# LM_180622.net
KiCad netlist of a schematic drawn in EAGLE
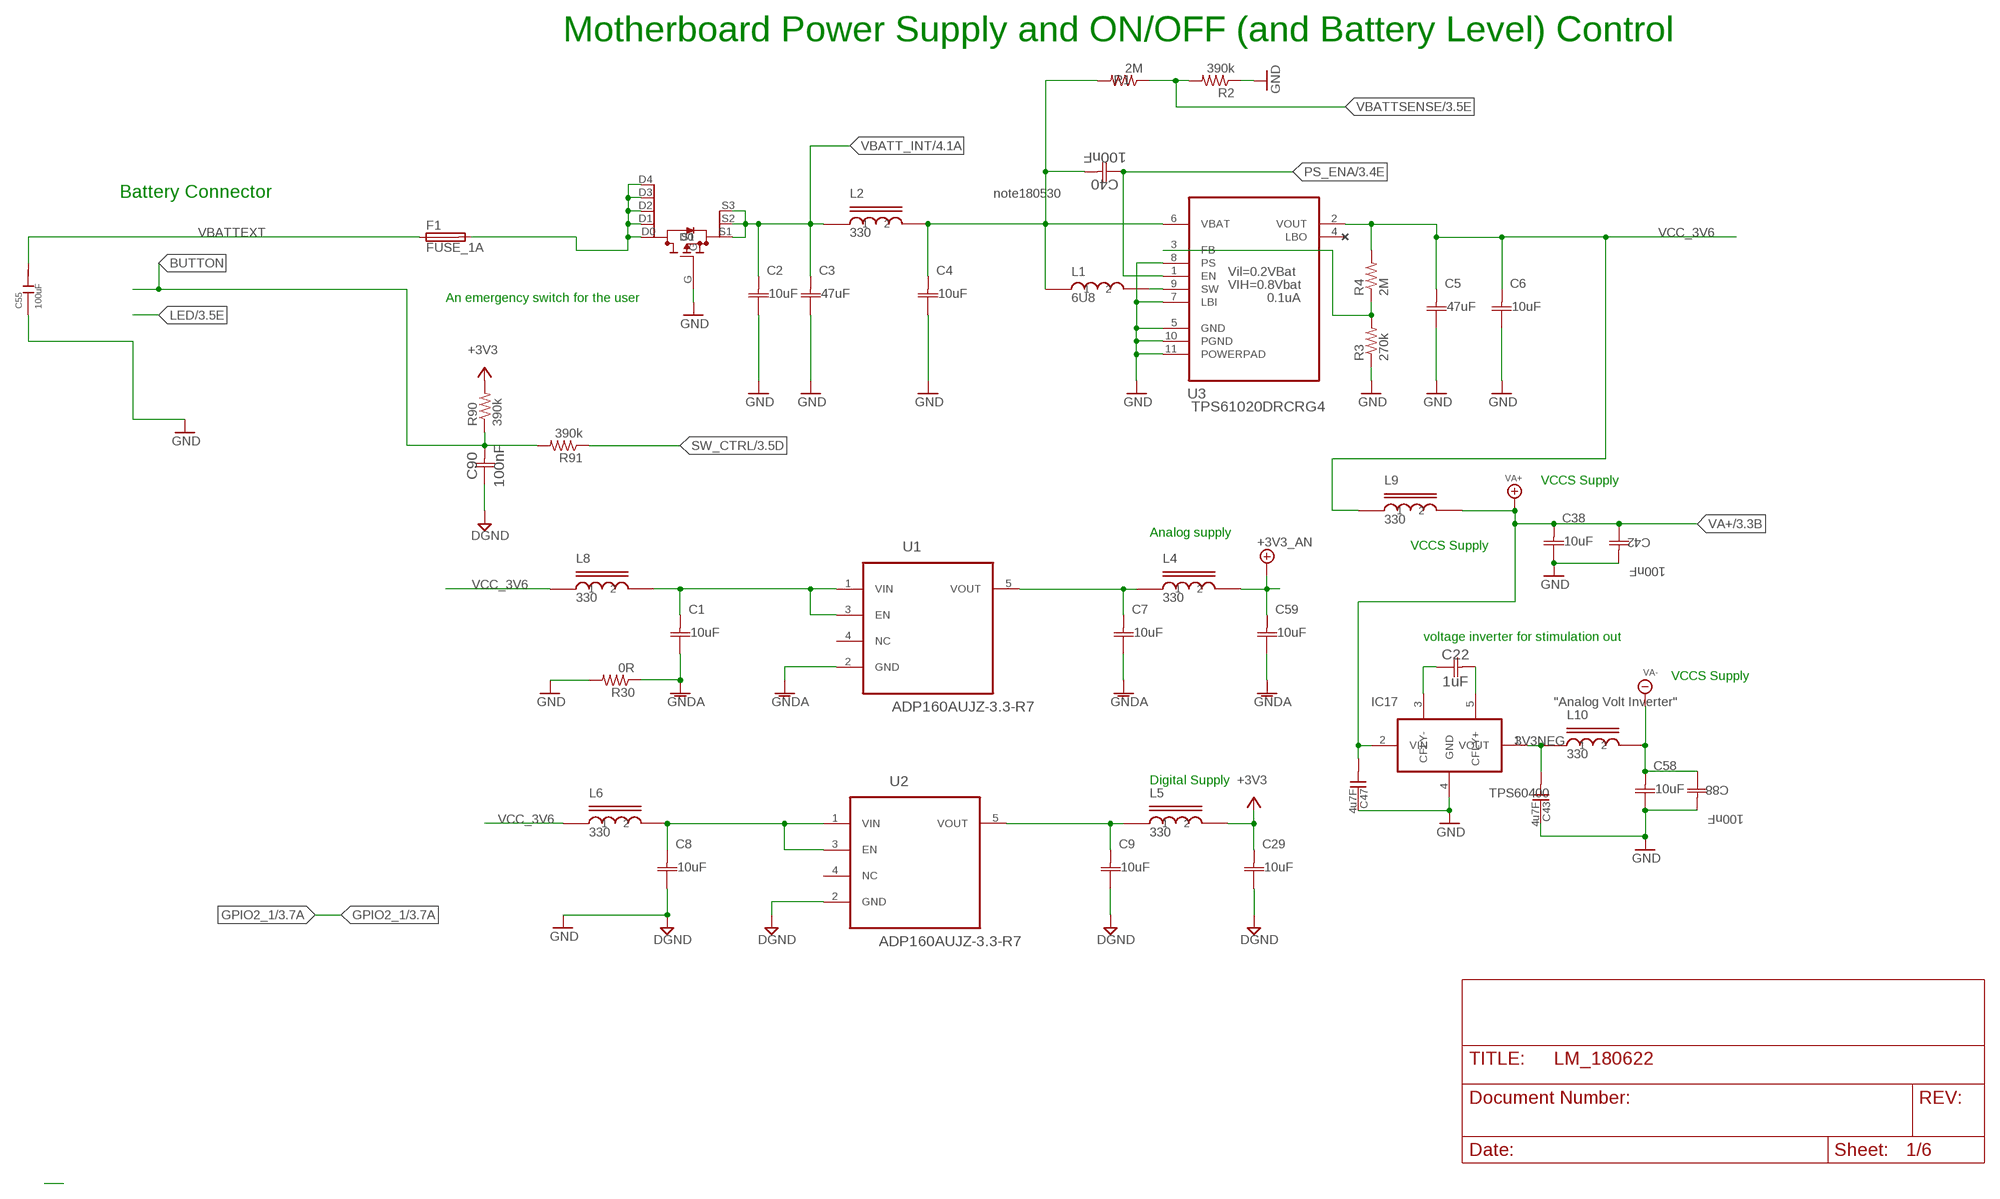
[diagram p0: schematic, sheet 1]
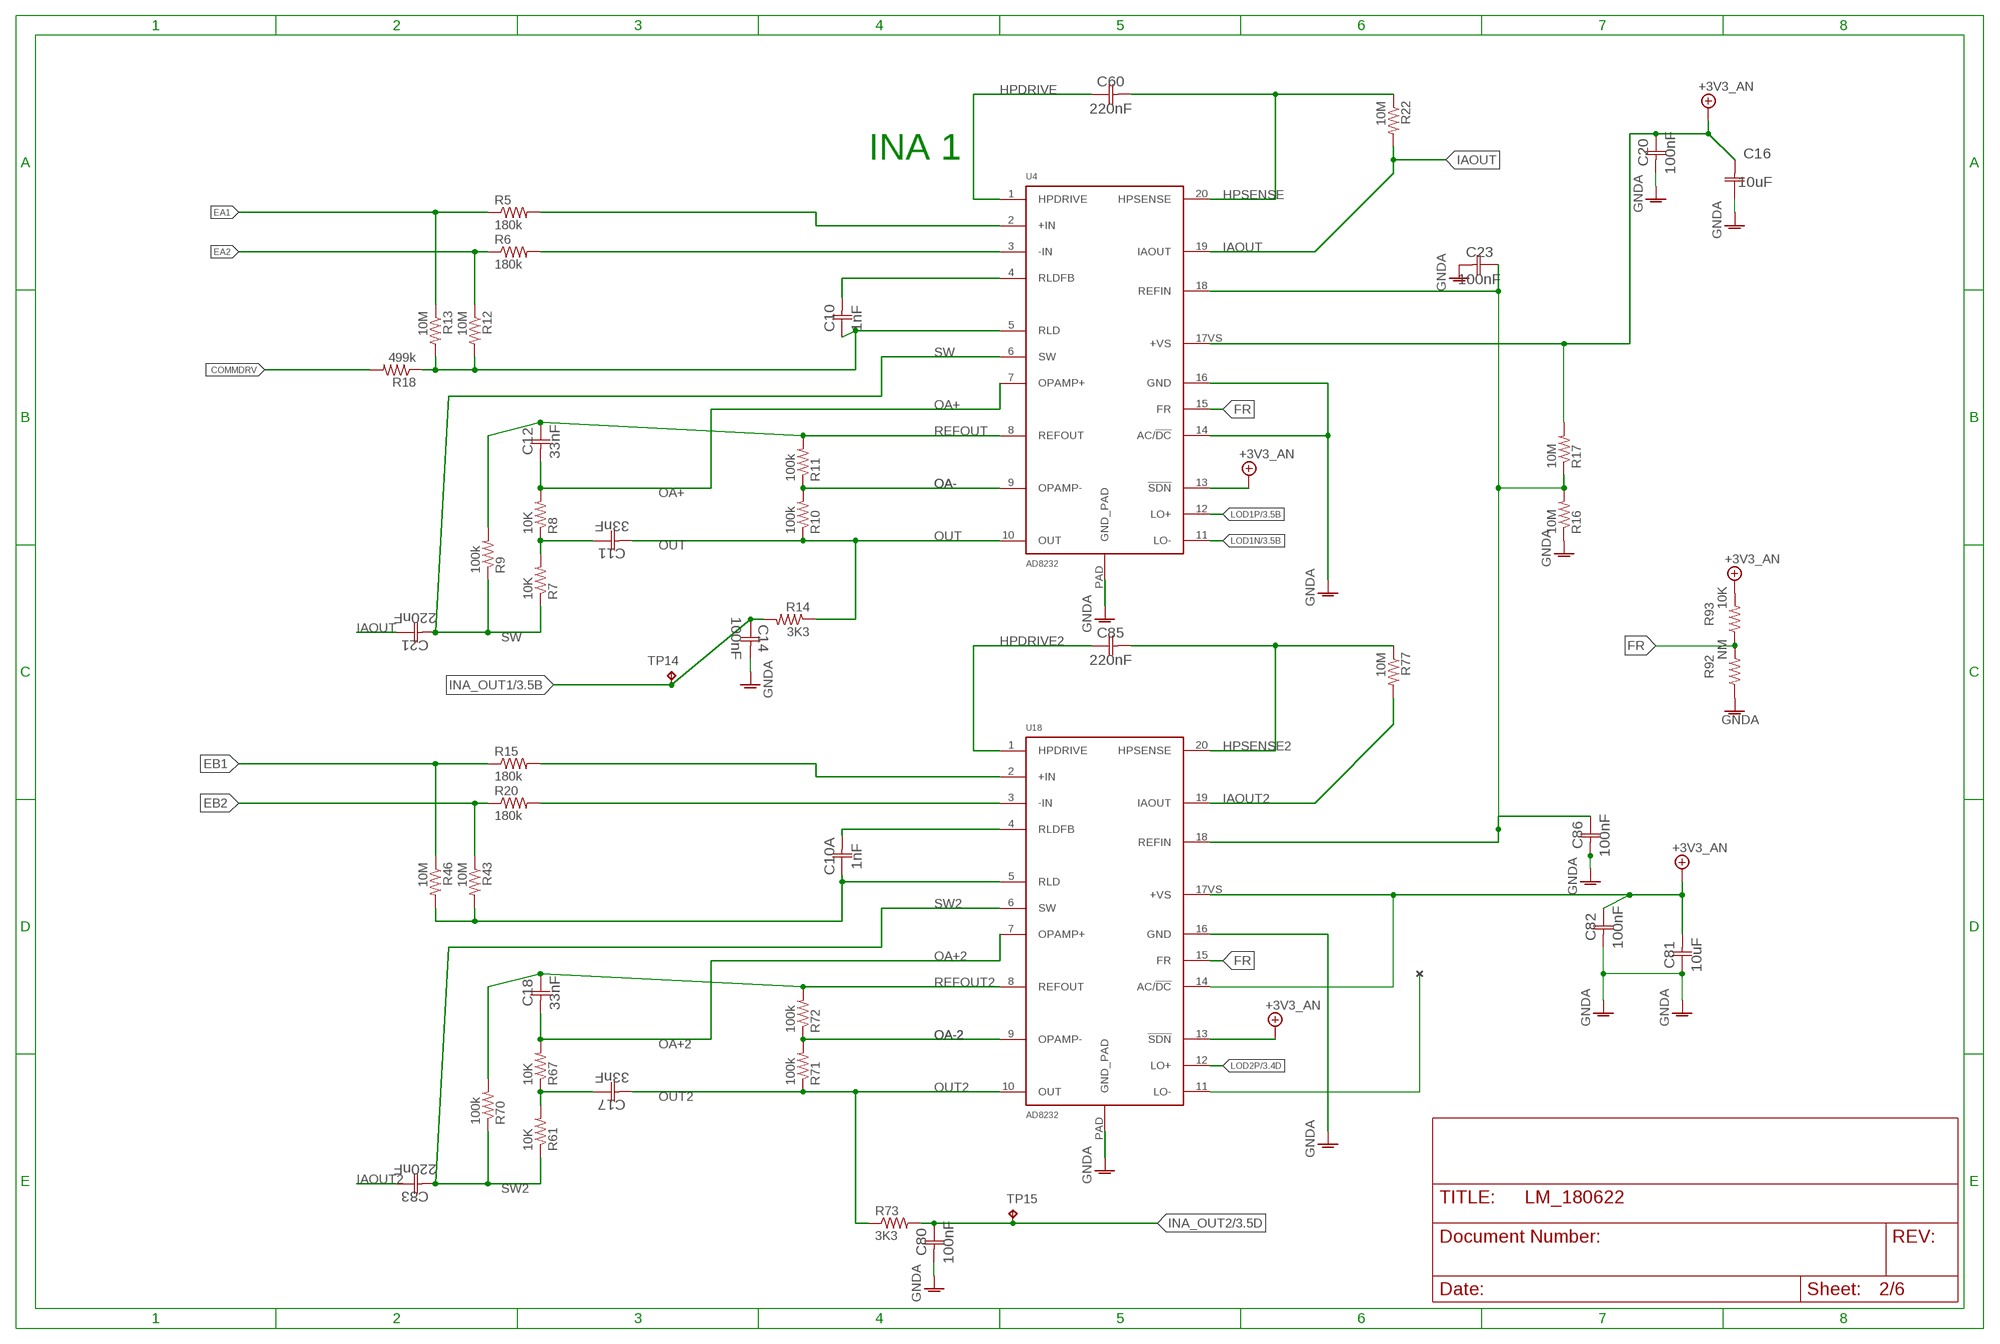
[diagram p1: schematic, sheet 2]
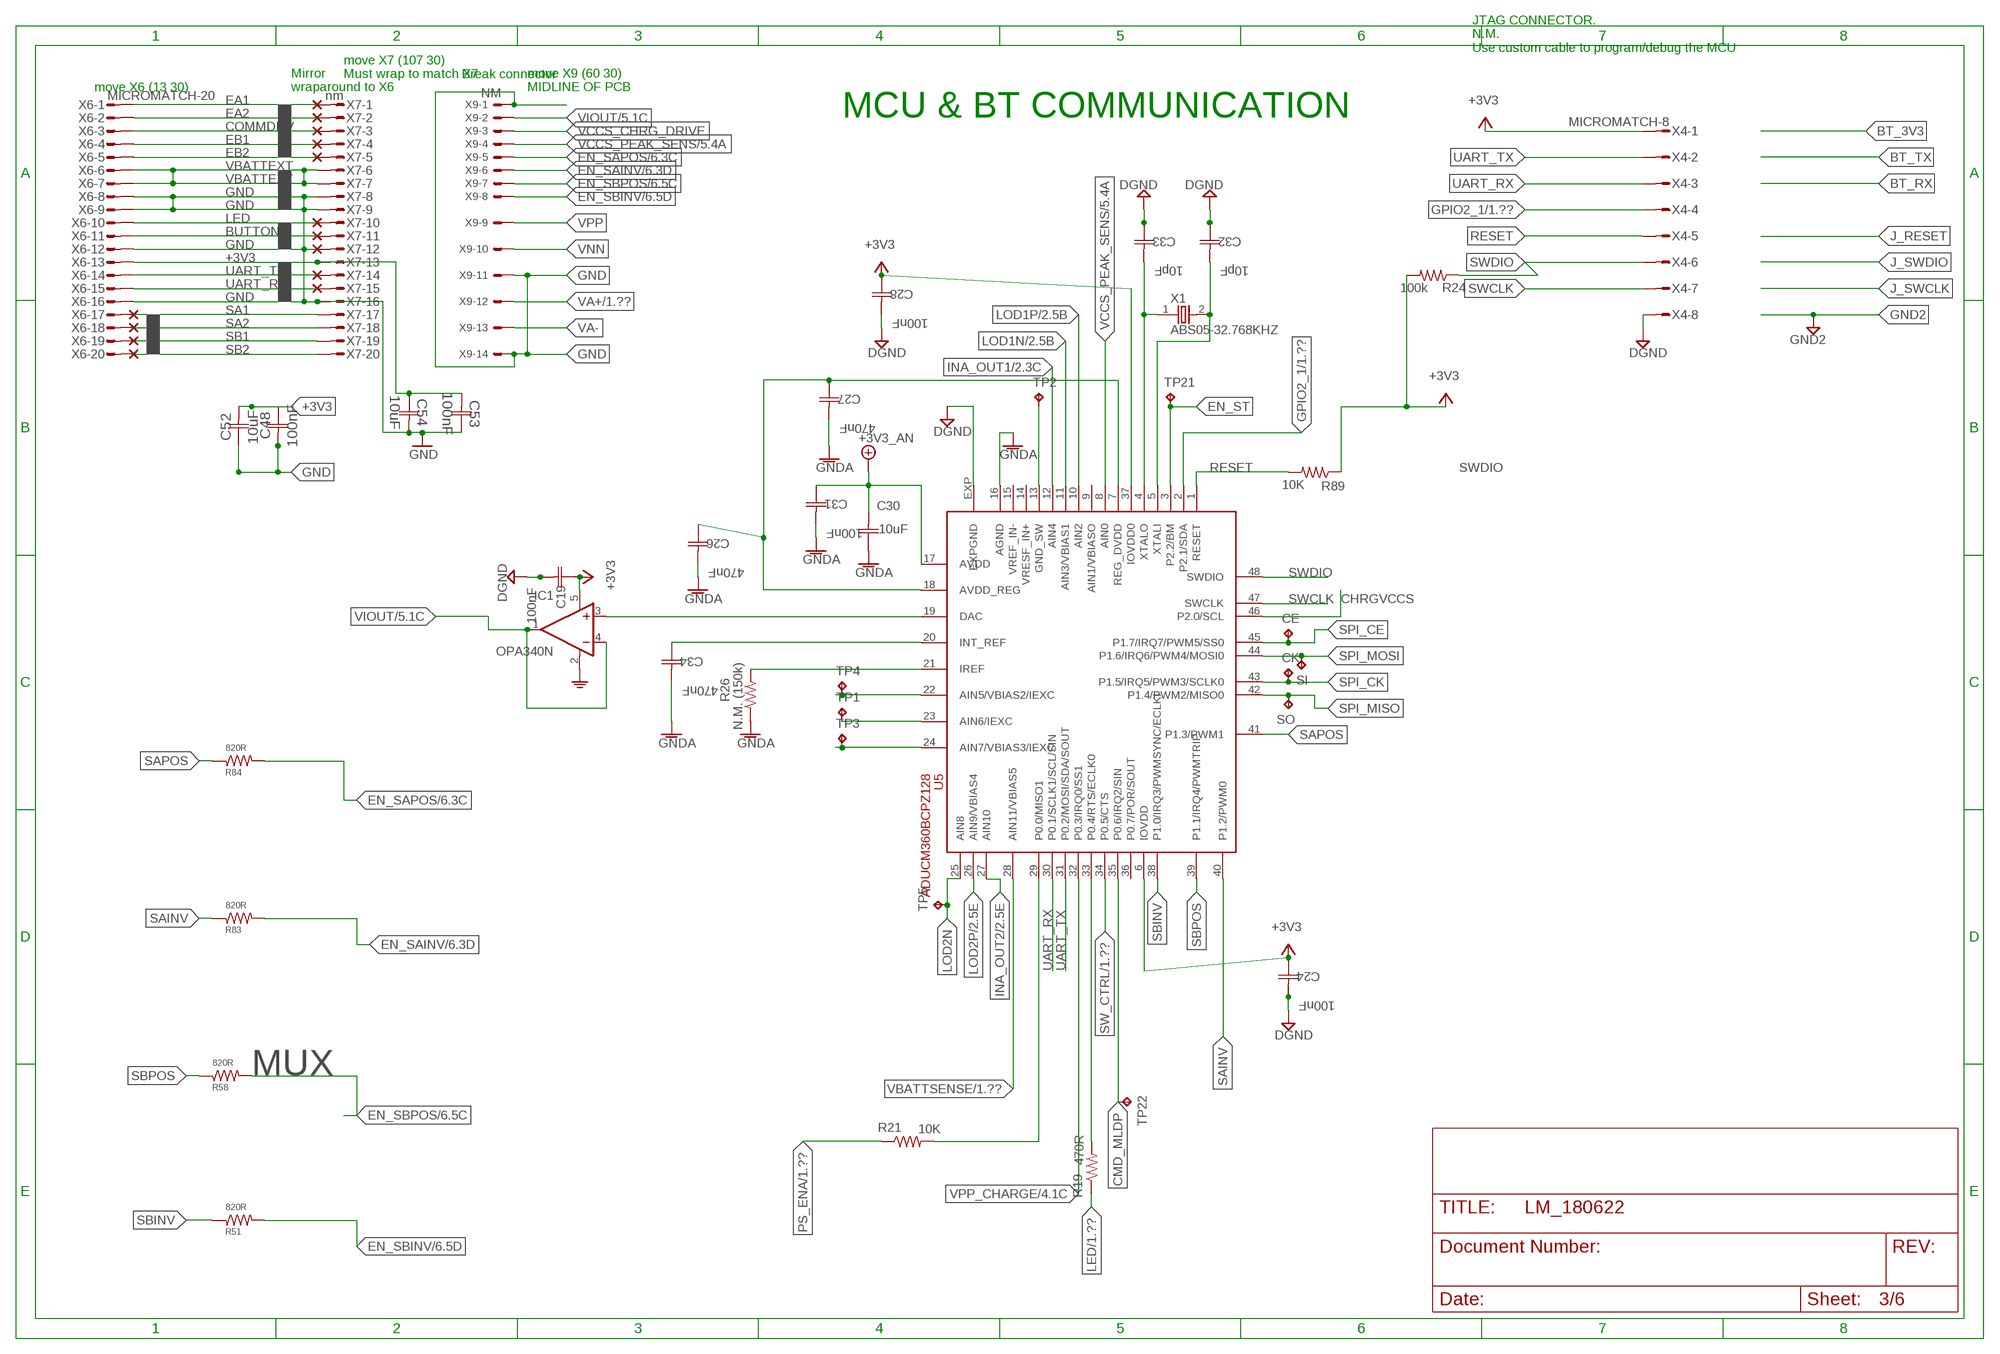
[diagram p2: schematic, sheet 3]
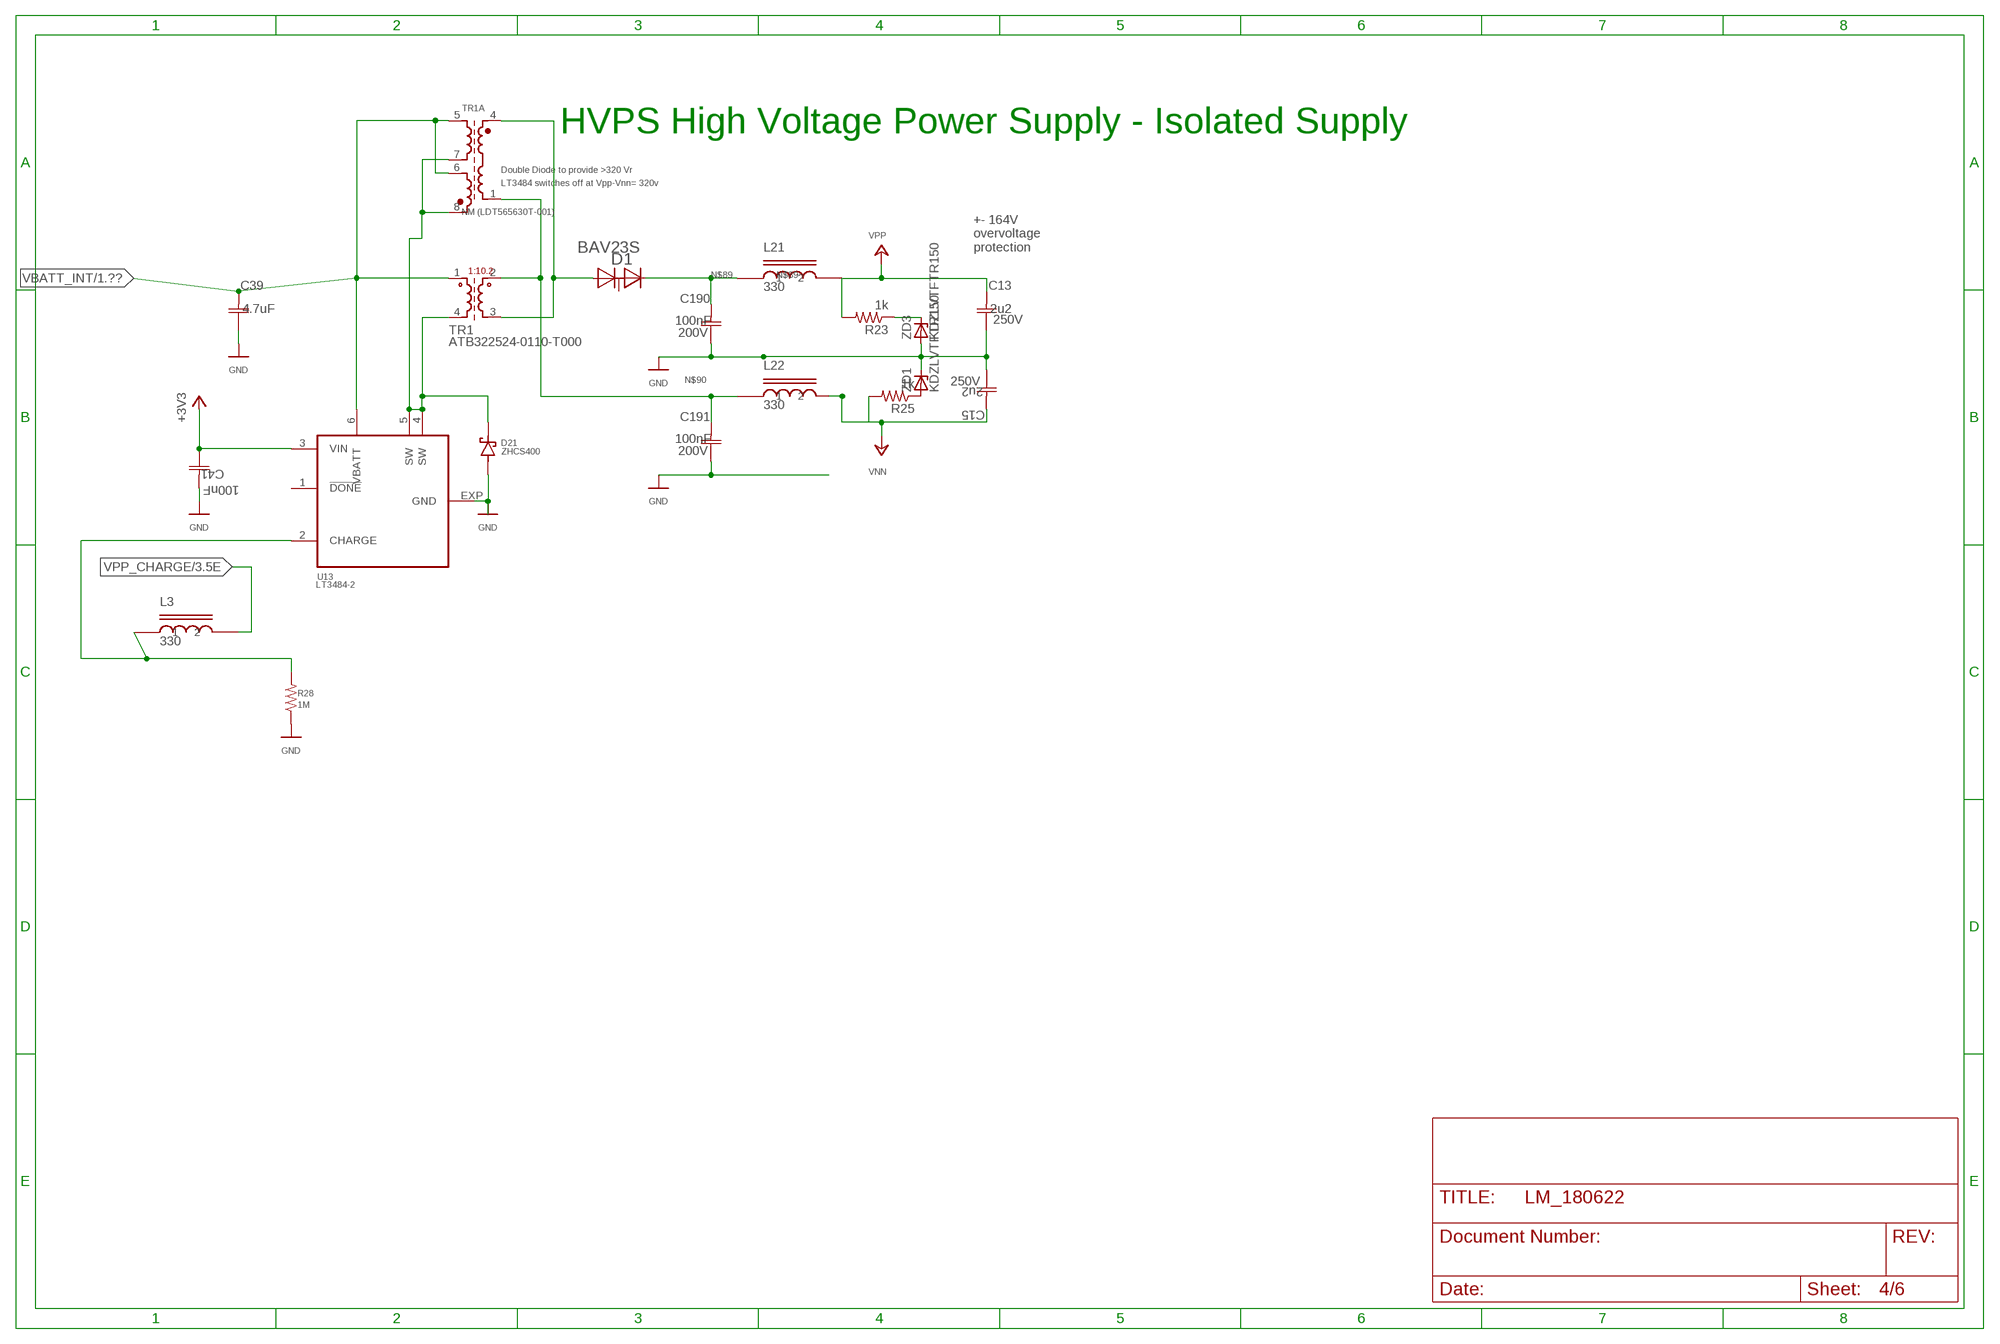
[diagram p3: schematic, sheet 4]
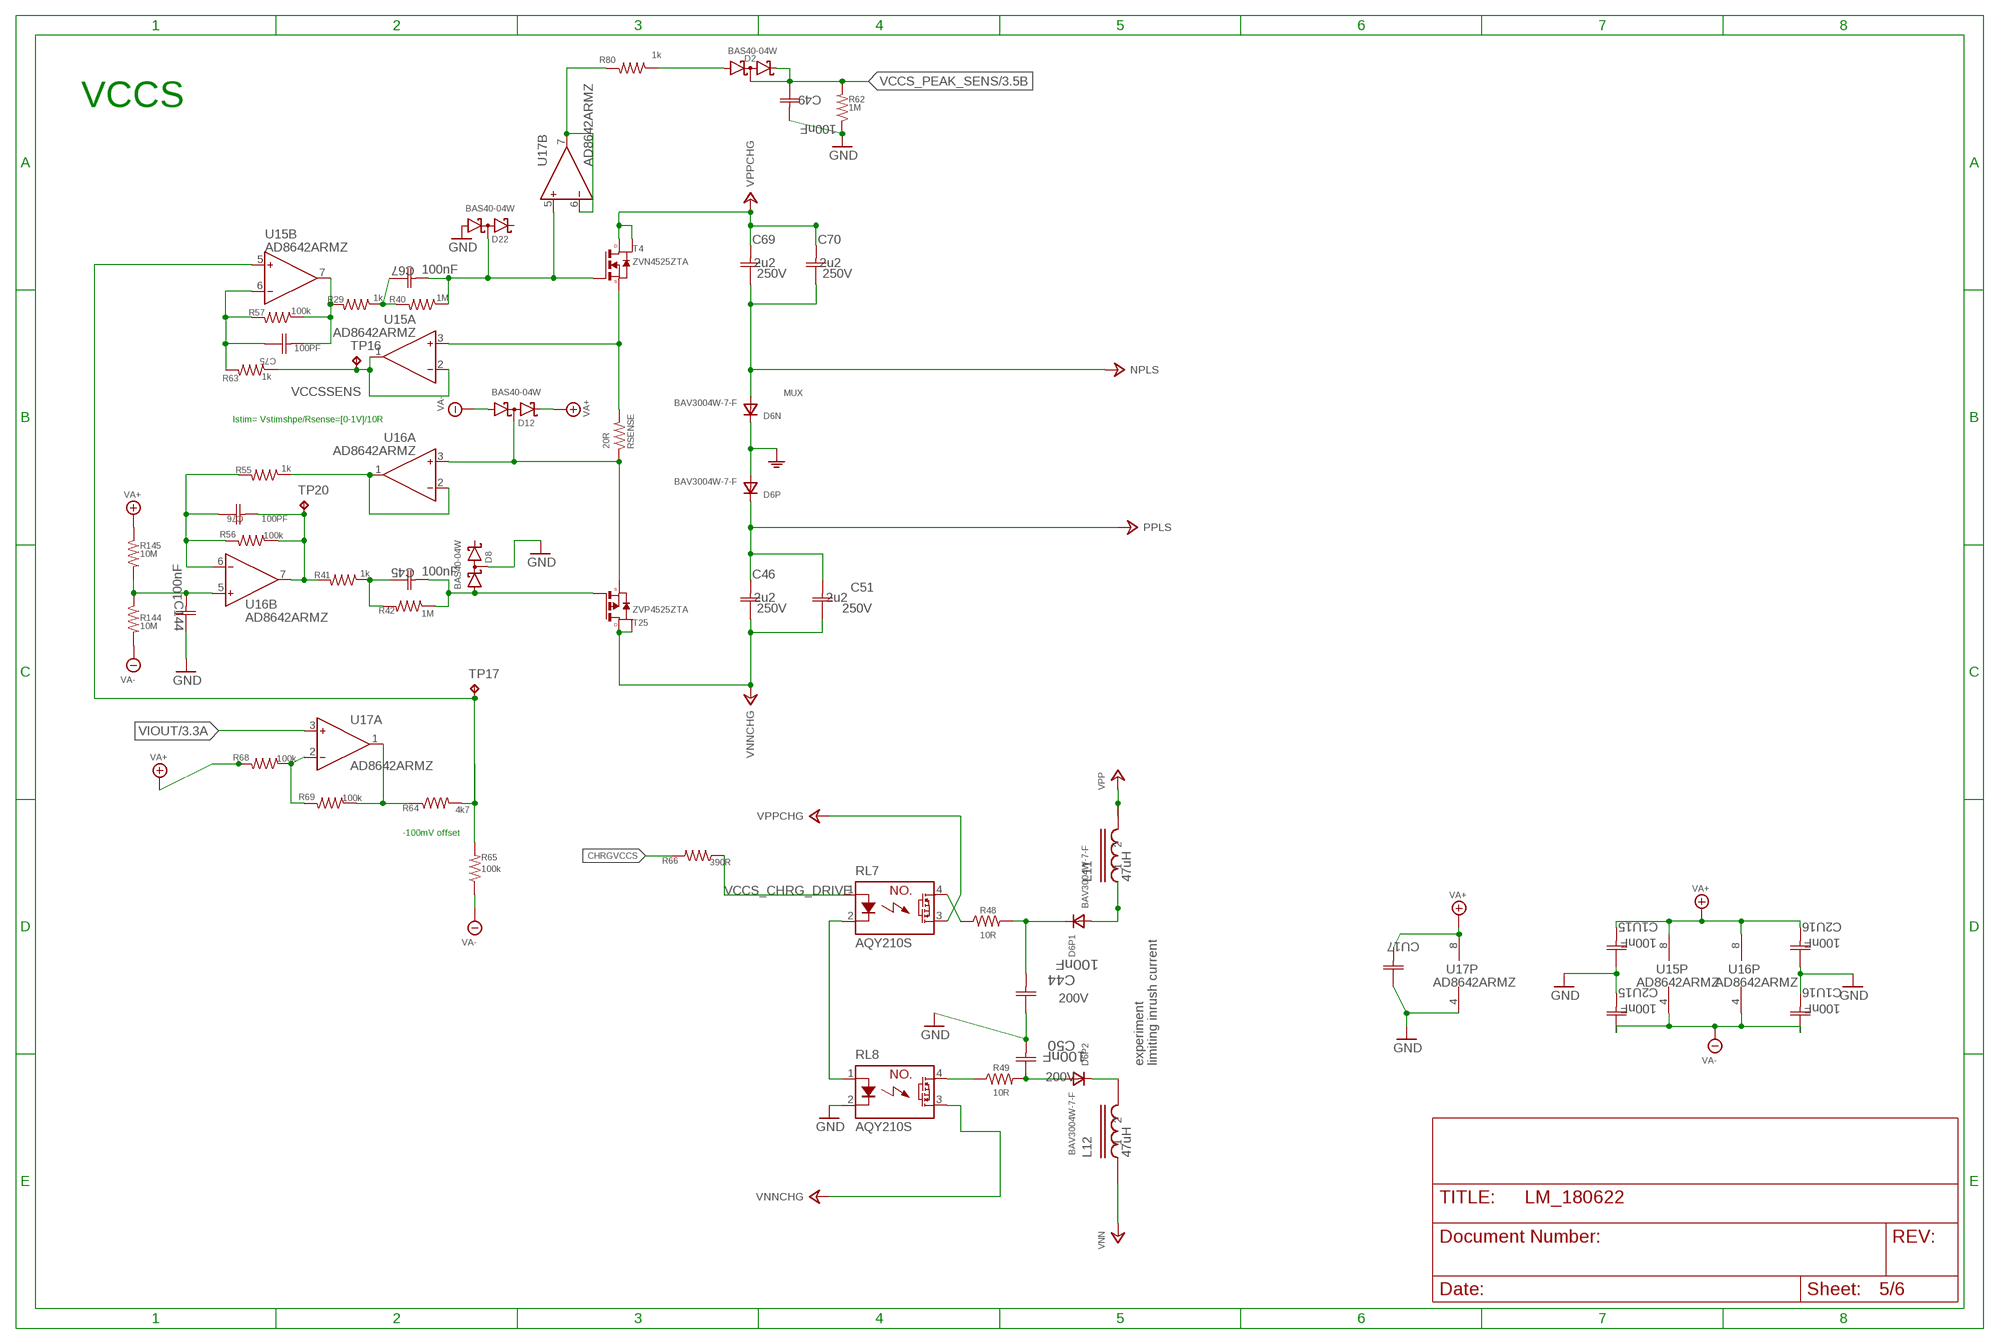
[diagram p4: schematic, sheet 5]
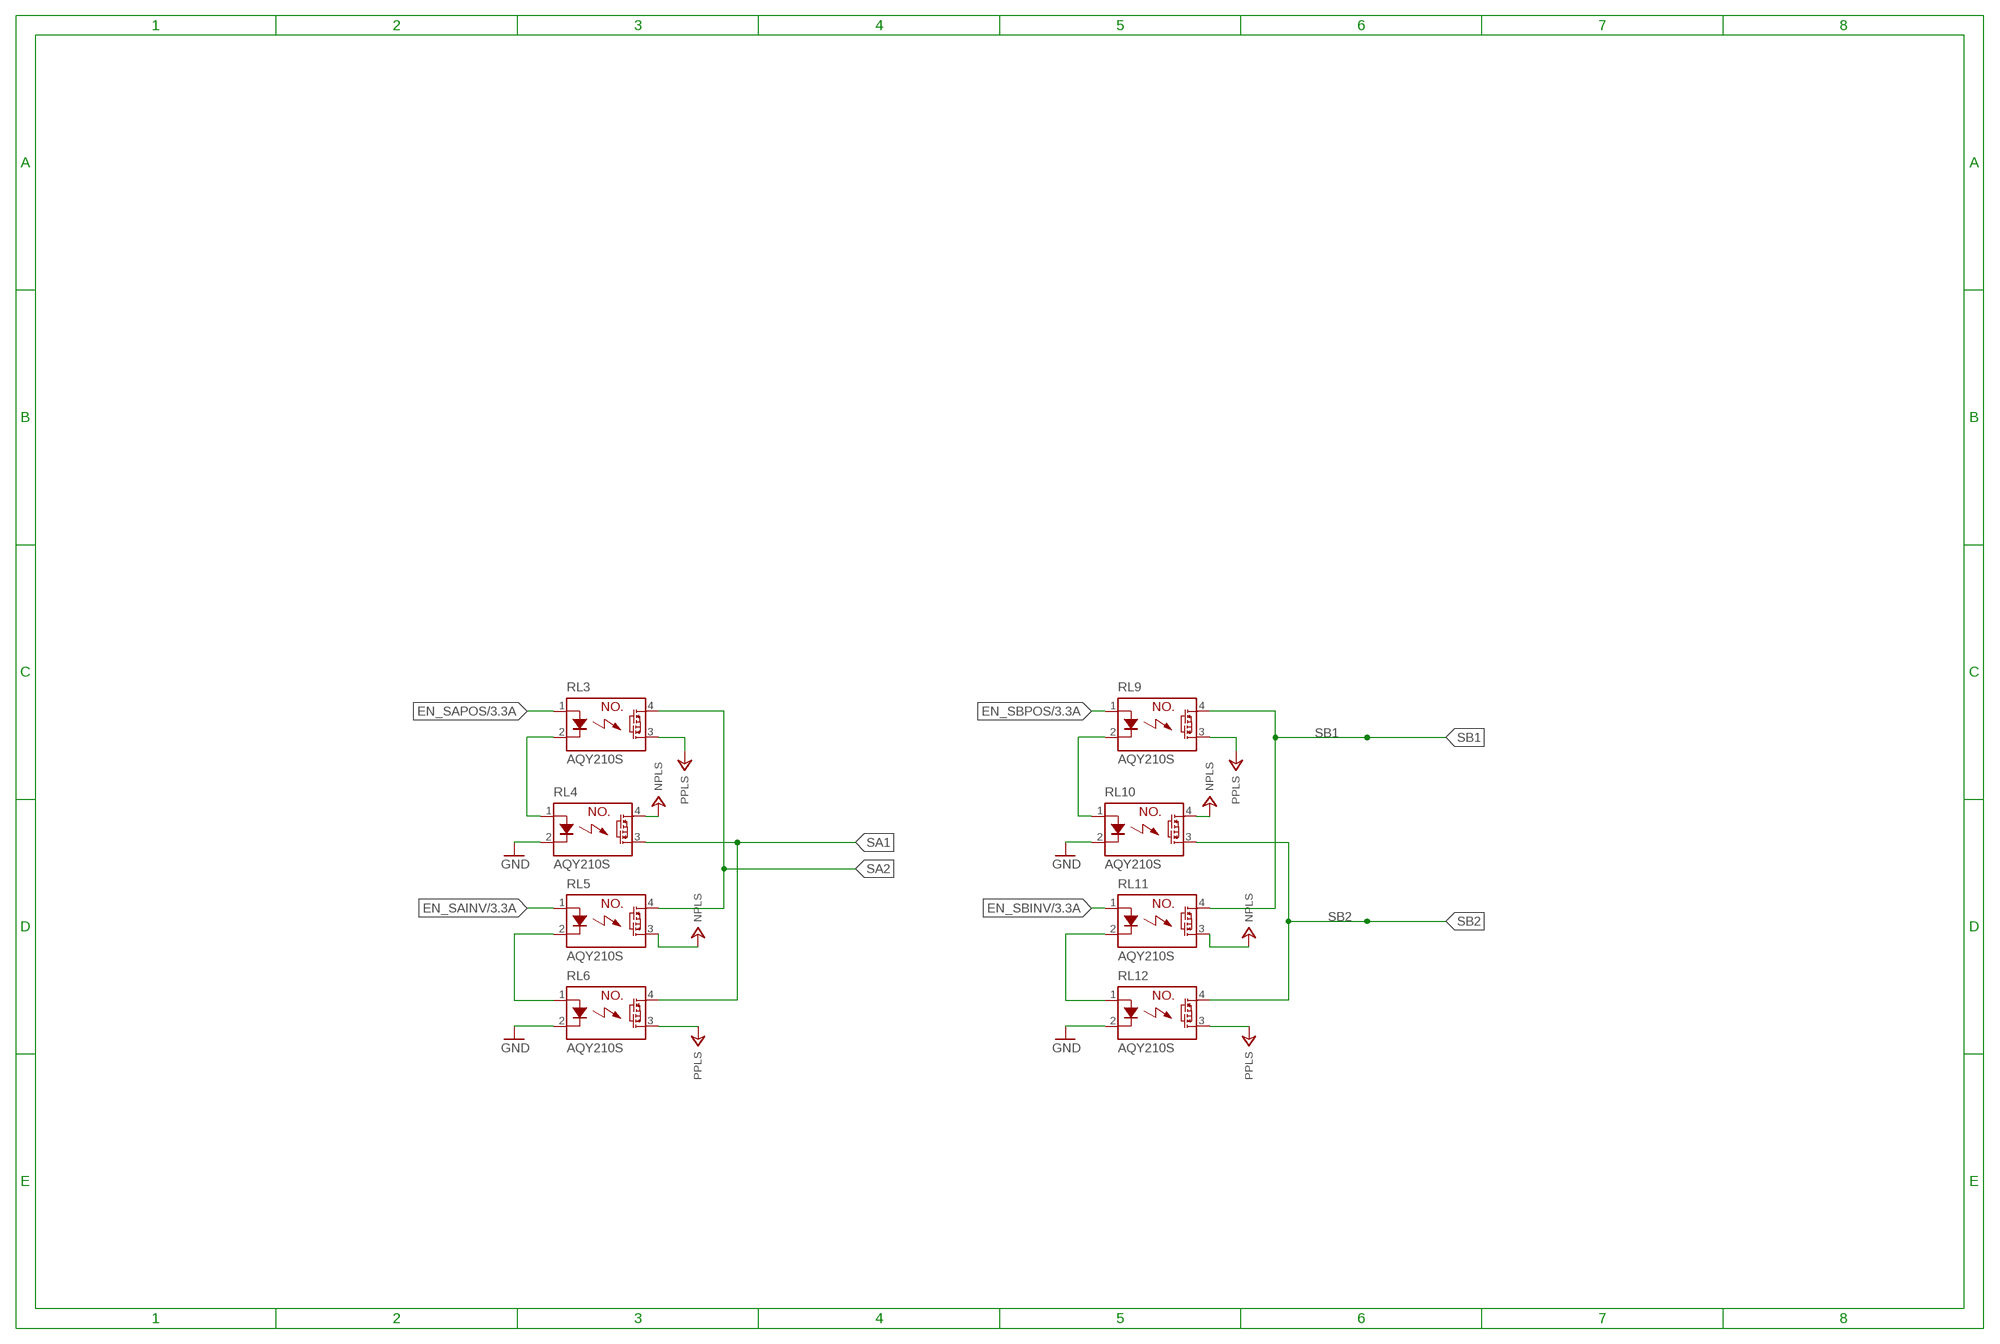
[diagram p5: schematic, sheet 6]

(export (version "E")
  (design (tool "Eeschema 10.0.6"))
  (components
    (comp (ref "C13")
      (value "2u2")
      (footprint "eagle-import:C2220K")
      (fields
        (field (name "MPN") "CGA9P3X7T2E225K250KA")
        (field (name "TOLERANCE") "±10%")
        (field (name "VOLTAGERATING") "250V")
        (field (name "MPN_1") "ECA-2GHG2R2")
      )
      (libsource (lib "eagle-import") (part "CGA9P3X7T2E225K250KA"))
    )
    (comp (ref "C15")
      (value "2u2")
      (footprint "eagle-import:C2220K")
      (fields
        (field (name "MPN") "CGA9P3X7T2E225K250KA")
        (field (name "TOLERANCE") "±10%")
        (field (name "VOLTAGERATING") "250V")
        (field (name "MPN_1") "ECA-2GHG2R2")
      )
      (libsource (lib "eagle-import") (part "CGA9P3X7T2E225K250KA"))
    )
    (comp (ref "C39")
      (value "4.7uF")
      (footprint "eagle-import:C0603")
      (fields (field (name "MPN") "C0603C475K9PACTU") (field (name "TOLERANCE") "±10%"))
      (libsource (lib "eagle-import") (part "C0603C475K9PACTU"))
    )
    (comp (ref "C41")
      (value "100nF")
      (footprint "eagle-import:C0603")
      (fields (field (name "MPN") "C0603C104K5RACTU") (field (name "TOLERANCE") " ±10%"))
      (libsource (lib "eagle-import") (part "C100NFC0603"))
    )
    (comp (ref "C190")
      (value "100nF")
      (footprint "eagle-import:1206")
      (fields
        (field (name "MPN") "12062C104KAT2A")
        (field (name "TOLERANCE") "±10%")
        (field (name "VOLTAGERATING") "200V")
      )
      (libsource (lib "eagle-import") (part "12062C104KAT2A"))
    )
    (comp (ref "C191")
      (value "100nF")
      (footprint "eagle-import:1206")
      (fields
        (field (name "MPN") "12062C104KAT2A")
        (field (name "TOLERANCE") "±10%")
        (field (name "VOLTAGERATING") "200V")
      )
      (libsource (lib "eagle-import") (part "12062C104KAT2A"))
    )
    (comp (ref "D1")
      (value "BAV23S")
      (footprint "eagle-import:SOT23")
      (fields (field (name "MPN") "BAV23S-7-F"))
      (libsource (lib "eagle-import") (part "BAV23S"))
    )
    (comp (ref "D21")
      (value "ZHCS400")
      (footprint "eagle-import:SOD323")
      (libsource (lib "eagle-import") (part "ZHCS400"))
    )
    (comp (ref "L3")
      (value "330")
      (footprint "eagle-import:L0603")
      (fields (field (name "PARTNO") "MMZ1608B301C"))
      (libsource (lib "eagle-import") (part "MMZ1608B301C"))
    )
    (comp (ref "L21")
      (value "330")
      (footprint "eagle-import:L0603")
      (fields (field (name "PARTNO") "MMZ1608B301C"))
      (libsource (lib "eagle-import") (part "MMZ1608B301C"))
    )
    (comp (ref "L22")
      (value "330")
      (footprint "eagle-import:L0603")
      (fields (field (name "PARTNO") "MMZ1608B301C"))
      (libsource (lib "eagle-import") (part "MMZ1608B301C"))
    )
    (comp (ref "R23")
      (value "1k")
      (footprint "eagle-import:R0603")
      (libsource (lib "eagle-import") (part "R1KR0603"))
    )
    (comp (ref "R25")
      (value "1k")
      (footprint "eagle-import:R0603")
      (libsource (lib "eagle-import") (part "R1KR0603"))
    )
    (comp (ref "R28")
      (value "1M")
      (footprint "eagle-import:R0603")
      (fields (field (name "OC_NEWARK") "unknown"))
      (libsource (lib "eagle-import") (part "R1MR0603"))
    )
    (comp (ref "TR1")
      (value "ATB322524-0110-T000")
      (footprint "eagle-import:3225_4PIN")
      (libsource (lib "eagle-import") (part "ATB322524-0110-T000"))
    )
    (comp (ref "TR1A")
      (value "NM (LDT565630T-001)")
      (footprint "eagle-import:SM-E6")
      (libsource (lib "eagle-import") (part "LDT565630T-001"))
    )
    (comp (ref "U13")
      (value "LT3484-2")
      (footprint "eagle-import:DFN6-2X3")
      (fields
        (field (name "MPN") "LT3484EDCB-2")
        (field (name "DESCR") "Charge Pin. A low (<0.3V) to high (>1V) transition  on this pin puts the part into power delivery mode Bringing the pin low (<0.3V) will terminate")
      )
      (libsource (lib "eagle-import") (part "LT3484"))
    )
    (comp (ref "ZD1")
      (value "KDZLVTFTR150")
      (footprint "eagle-import:SOD123")
      (libsource (lib "eagle-import") (part "KDZLVTFTR150"))
    )
    (comp (ref "ZD3")
      (value "KDZLVTFTR150")
      (footprint "eagle-import:SOD123")
      (libsource (lib "eagle-import") (part "KDZLVTFTR150"))
    )
    (comp (ref "RL3")
      (value "AQY210S")
      (footprint "eagle-import:SOP04")
      (fields (field (name "MPN") "AQY210SX"))
      (libsource (lib "eagle-import") (part "AQY210S"))
    )
    (comp (ref "RL4")
      (value "AQY210S")
      (footprint "eagle-import:SOP04")
      (fields (field (name "MPN") "AQY210SX"))
      (libsource (lib "eagle-import") (part "AQY210S"))
    )
    (comp (ref "RL5")
      (value "AQY210S")
      (footprint "eagle-import:SOP04")
      (fields (field (name "MPN") "AQY210SX"))
      (libsource (lib "eagle-import") (part "AQY210S"))
    )
    (comp (ref "RL6")
      (value "AQY210S")
      (footprint "eagle-import:SOP04")
      (fields (field (name "MPN") "AQY210SX"))
      (libsource (lib "eagle-import") (part "AQY210S"))
    )
    (comp (ref "RL9")
      (value "AQY210S")
      (footprint "eagle-import:SOP04")
      (fields (field (name "MPN") "AQY210SX"))
      (libsource (lib "eagle-import") (part "AQY210S"))
    )
    (comp (ref "RL10")
      (value "AQY210S")
      (footprint "eagle-import:SOP04")
      (fields (field (name "MPN") "AQY210SX"))
      (libsource (lib "eagle-import") (part "AQY210S"))
    )
    (comp (ref "RL11")
      (value "AQY210S")
      (footprint "eagle-import:SOP04")
      (fields (field (name "MPN") "AQY210SX"))
      (libsource (lib "eagle-import") (part "AQY210S"))
    )
    (comp (ref "RL12")
      (value "AQY210S")
      (footprint "eagle-import:SOP04")
      (fields (field (name "MPN") "AQY210SX"))
      (libsource (lib "eagle-import") (part "AQY210S"))
    )
    (comp (ref "C1")
      (value "10uF")
      (footprint "eagle-import:C0603")
      (fields (field (name "MPN") "C0603C106M9PACTU") (field (name "TOLERANCE") "±20%"))
      (libsource (lib "eagle-import") (part "C0603C106M9PACTU"))
    )
    (comp (ref "C2")
      (value "10uF")
      (footprint "eagle-import:C0603")
      (fields (field (name "MPN") "C0603C106M9PACTU") (field (name "TOLERANCE") "±20%"))
      (libsource (lib "eagle-import") (part "C0603C106M9PACTU"))
    )
    (comp (ref "C3")
      (value "47uF")
      (footprint "eagle-import:C0805")
      (fields (field (name "MPN") "C0805C476M9PACTU") (field (name "TOLERANCE") "±20%"))
      (libsource (lib "eagle-import") (part "C0805C476M9PACTU"))
    )
    (comp (ref "C4")
      (value "10uF")
      (footprint "eagle-import:C0603")
      (fields (field (name "MPN") "C0603C106M9PACTU") (field (name "TOLERANCE") "±20%"))
      (libsource (lib "eagle-import") (part "C0603C106M9PACTU"))
    )
    (comp (ref "C5")
      (value "47uF")
      (footprint "eagle-import:C0805")
      (fields (field (name "MPN") "C0805C476M9PACTU") (field (name "TOLERANCE") "±20%"))
      (libsource (lib "eagle-import") (part "C0805C476M9PACTU"))
    )
    (comp (ref "C6")
      (value "10uF")
      (footprint "eagle-import:C0603")
      (fields (field (name "MPN") "C0603C106M9PACTU") (field (name "TOLERANCE") "±20%"))
      (libsource (lib "eagle-import") (part "C0603C106M9PACTU"))
    )
    (comp (ref "C7")
      (value "10uF")
      (footprint "eagle-import:C0603")
      (fields (field (name "MPN") "C0603C106M9PACTU") (field (name "TOLERANCE") "±20%"))
      (libsource (lib "eagle-import") (part "C0603C106M9PACTU"))
    )
    (comp (ref "C8")
      (value "10uF")
      (footprint "eagle-import:C0603")
      (fields (field (name "MPN") "C0603C106M9PACTU") (field (name "TOLERANCE") "±20%"))
      (libsource (lib "eagle-import") (part "C0603C106M9PACTU"))
    )
    (comp (ref "C9")
      (value "10uF")
      (footprint "eagle-import:C0603")
      (fields (field (name "MPN") "C0603C106M9PACTU") (field (name "TOLERANCE") "±20%"))
      (libsource (lib "eagle-import") (part "C0603C106M9PACTU"))
    )
    (comp (ref "C22")
      (value "1uF")
      (footprint "eagle-import:0603-CAP")
      (fields (field (name "MPN") "C0603C105K3PACTU") (field (name "TOLERANCE") "±10%"))
      (libsource (lib "eagle-import") (part "C0603C105K3PACTU"))
    )
    (comp (ref "C29")
      (value "10uF")
      (footprint "eagle-import:C0603")
      (fields (field (name "MPN") "C0603C106M9PACTU") (field (name "TOLERANCE") "±20%"))
      (libsource (lib "eagle-import") (part "C0603C106M9PACTU"))
    )
    (comp (ref "C38")
      (value "10uF")
      (footprint "eagle-import:C0603")
      (fields (field (name "MPN") "C0603C106M9PACTU") (field (name "TOLERANCE") "±20%"))
      (libsource (lib "eagle-import") (part "C0603C106M9PACTU"))
    )
    (comp (ref "C40")
      (value "100nF")
      (footprint "eagle-import:C0603")
      (fields (field (name "MPN") "C0603C104K5RACTU") (field (name "TOLERANCE") " ±10%"))
      (libsource (lib "eagle-import") (part "C100NFC0603"))
    )
    (comp (ref "C42")
      (value "100nF")
      (footprint "eagle-import:C0603")
      (fields (field (name "MPN") "C0603C104K5RACTU") (field (name "TOLERANCE") " ±10%"))
      (libsource (lib "eagle-import") (part "C100NFC0603"))
    )
    (comp (ref "C43")
      (value "4u7F")
      (footprint "eagle-import:C0805")
      (libsource (lib "eagle-import") (part "C0805_4U7"))
    )
    (comp (ref "C47")
      (value "4u7F")
      (footprint "eagle-import:C0805")
      (libsource (lib "eagle-import") (part "C0805_4U7"))
    )
    (comp (ref "C55")
      (value "100uF")
      (footprint "eagle-import:C1210")
      (fields (field (name "MPN") "C3225X5R0J107M250AC") (field (name "MPN_1") "JMK325BJ107MY-T"))
      (libsource (lib "eagle-import") (part "C100UF-6V3-1210"))
    )
    (comp (ref "C58")
      (value "10uF")
      (footprint "eagle-import:C0603")
      (fields (field (name "MPN") "C0603C106M9PACTU") (field (name "TOLERANCE") "±20%"))
      (libsource (lib "eagle-import") (part "C0603C106M9PACTU"))
    )
    (comp (ref "C59")
      (value "10uF")
      (footprint "eagle-import:C0603")
      (fields (field (name "MPN") "C0603C106M9PACTU") (field (name "TOLERANCE") "±20%"))
      (libsource (lib "eagle-import") (part "C0603C106M9PACTU"))
    )
    (comp (ref "C88")
      (value "100nF")
      (footprint "eagle-import:C0603")
      (fields (field (name "MPN") "C0603C104K5RACTU") (field (name "TOLERANCE") " ±10%"))
      (libsource (lib "eagle-import") (part "C100NFC0603"))
    )
    (comp (ref "C90")
      (value "100nF")
      (footprint "eagle-import:C0603")
      (fields (field (name "MPN") "C0603C104K5RACTU") (field (name "TOLERANCE") " ±10%"))
      (libsource (lib "eagle-import") (part "C100NFC0603"))
    )
    (comp (ref "F1")
      (value "FUSE_1A")
      (footprint "eagle-import:C0805")
      (fields (field (name "MPN") "0805L100WR"))
      (libsource (lib "eagle-import") (part "FUSE_1A"))
    )
    (comp (ref "IC17")
      (value "TPS60400")
      (footprint "eagle-import:SOT23-5")
      (fields (field (name "MPN") "TPS60400DBVR"))
      (libsource (lib "eagle-import") (part "TPS60400"))
    )
    (comp (ref "L1")
      (value "6U8")
      (footprint "eagle-import:SMT_POWER_IND_B82462G4")
      (fields (field (name "MPN") "B82462G4682M") (field (name "MPN_1") "B82462G4682M000"))
      (libsource (lib "eagle-import") (part "B82462G4682M"))
    )
    (comp (ref "L2")
      (value "330")
      (footprint "eagle-import:L0603")
      (fields (field (name "PARTNO") "MMZ1608B301C"))
      (libsource (lib "eagle-import") (part "MMZ1608B301C"))
    )
    (comp (ref "L4")
      (value "330")
      (footprint "eagle-import:L0603")
      (fields (field (name "PARTNO") "MMZ1608B301C"))
      (libsource (lib "eagle-import") (part "MMZ1608B301C"))
    )
    (comp (ref "L5")
      (value "330")
      (footprint "eagle-import:L0603")
      (fields (field (name "PARTNO") "MMZ1608B301C"))
      (libsource (lib "eagle-import") (part "MMZ1608B301C"))
    )
    (comp (ref "L6")
      (value "330")
      (footprint "eagle-import:L0603")
      (fields (field (name "PARTNO") "MMZ1608B301C"))
      (libsource (lib "eagle-import") (part "MMZ1608B301C"))
    )
    (comp (ref "L8")
      (value "330")
      (footprint "eagle-import:L0603")
      (fields (field (name "PARTNO") "MMZ1608B301C"))
      (libsource (lib "eagle-import") (part "MMZ1608B301C"))
    )
    (comp (ref "L9")
      (value "330")
      (footprint "eagle-import:L0603")
      (fields (field (name "PARTNO") "MMZ1608B301C"))
      (libsource (lib "eagle-import") (part "MMZ1608B301C"))
    )
    (comp (ref "L10")
      (value "330")
      (footprint "eagle-import:L0603")
      (fields (field (name "PARTNO") "MMZ1608B301C"))
      (libsource (lib "eagle-import") (part "MMZ1608B301C"))
    )
    (comp (ref "PMOS1")
      (value "SIS407DN")
      (footprint "eagle-import:POWERPAK1212-8SINGLE")
      (fields (field (name "MPN") "SIS407DN-T1-GE3"))
      (libsource (lib "eagle-import") (part "SIS407DN"))
    )
    (comp (ref "R1")
      (value "2M")
      (footprint "eagle-import:R0603")
      (fields (field (name "OC_NEWARK") "unknown"))
      (libsource (lib "eagle-import") (part "R2MR0603"))
    )
    (comp (ref "R2")
      (value "390k")
      (footprint "eagle-import:R0603")
      (fields (field (name "OC_NEWARK") "unknown"))
      (libsource (lib "eagle-import") (part "R390KR0603"))
    )
    (comp (ref "R3")
      (value "270k")
      (footprint "eagle-import:R0603")
      (fields
        (field (name "MPN") "MC0603N270K500CT")
        (field (name "MPN_1") "MC0603N270K500CT")
        (field (name "OC_NEWARK") "06R5158")
      )
      (libsource (lib "eagle-import") (part "R270KR0603"))
    )
    (comp (ref "R4")
      (value "2M")
      (footprint "eagle-import:R0603")
      (fields (field (name "OC_NEWARK") "unknown"))
      (libsource (lib "eagle-import") (part "R2MR0603"))
    )
    (comp (ref "R30")
      (value "0R")
      (footprint "eagle-import:R0603")
      (fields (field (name "OC_EC") "CR0603-J/-000ELF") (field (name "OC_NEWARK") "02J2264"))
      (libsource (lib "eagle-import") (part "R0RR0603"))
    )
    (comp (ref "R90")
      (value "390k")
      (footprint "eagle-import:R0603")
      (fields (field (name "OC_NEWARK") "unknown"))
      (libsource (lib "eagle-import") (part "R390KR0603"))
    )
    (comp (ref "R91")
      (value "390k")
      (footprint "eagle-import:R0603")
      (fields (field (name "OC_NEWARK") "unknown"))
      (libsource (lib "eagle-import") (part "R390KR0603"))
    )
    (comp (ref "U1")
      (value "ADP160AUJZ-3.3-R7")
      (footprint "eagle-import:SOT95P280X100-5N")
      (fields (field (name "MPN") "MIC5255-3.3YM5-TR") (field (name "OC_NEWARK") "30AC9897"))
      (libsource (lib "eagle-import") (part "ADP160AUJZ-3.3-R7"))
    )
    (comp (ref "U2")
      (value "ADP160AUJZ-3.3-R7")
      (footprint "eagle-import:SOT95P280X100-5N")
      (fields (field (name "MPN") "MIC5255-3.3YM5-TR") (field (name "OC_NEWARK") "30AC9897"))
      (libsource (lib "eagle-import") (part "ADP160AUJZ-3.3-R7"))
    )
    (comp (ref "U3")
      (value "TPS61020DRCRG4")
      (footprint "eagle-import:SON50P300X300X100-11N")
      (libsource (lib "eagle-import") (part "TPS61020DRCRG4"))
    )
    (comp (ref "C10")
      (value "1nF")
      (footprint "eagle-import:C0603")
      (fields (field (name "MPN") "C0603C102J5GACTU") (field (name "TOLERANCE") "±5%"))
      (libsource (lib "eagle-import") (part "C0603C102J5GACTU"))
    )
    (comp (ref "C10A")
      (value "1nF")
      (footprint "eagle-import:C0603")
      (fields (field (name "MPN") "C0603C102J5GACTU") (field (name "TOLERANCE") "±5%"))
      (libsource (lib "eagle-import") (part "C0603C102J5GACTU"))
    )
    (comp (ref "C11")
      (value "33nF")
      (footprint "eagle-import:C0603")
      (fields (field (name "TOLERANCE") "±10%") (field (name "OC_NEWARK") "unknown"))
      (libsource (lib "eagle-import") (part "C33NFC0603"))
    )
    (comp (ref "C12")
      (value "33nF")
      (footprint "eagle-import:C0603")
      (fields (field (name "TOLERANCE") "±10%") (field (name "OC_NEWARK") "unknown"))
      (libsource (lib "eagle-import") (part "C33NFC0603"))
    )
    (comp (ref "C14")
      (value "100nF")
      (footprint "eagle-import:C0603")
      (fields (field (name "MPN") "C0603C104K5RACTU") (field (name "TOLERANCE") " ±10%"))
      (libsource (lib "eagle-import") (part "C100NFC0603"))
    )
    (comp (ref "C16")
      (value "10uF")
      (footprint "eagle-import:C0603")
      (fields (field (name "MPN") "C0603C106M9PACTU") (field (name "TOLERANCE") "±20%"))
      (libsource (lib "eagle-import") (part "C0603C106M9PACTU"))
    )
    (comp (ref "C17")
      (value "33nF")
      (footprint "eagle-import:C0603")
      (fields (field (name "TOLERANCE") "±10%") (field (name "OC_NEWARK") "unknown"))
      (libsource (lib "eagle-import") (part "C33NFC0603"))
    )
    (comp (ref "C18")
      (value "33nF")
      (footprint "eagle-import:C0603")
      (fields (field (name "TOLERANCE") "±10%") (field (name "OC_NEWARK") "unknown"))
      (libsource (lib "eagle-import") (part "C33NFC0603"))
    )
    (comp (ref "C20")
      (value "100nF")
      (footprint "eagle-import:C0603")
      (fields (field (name "MPN") "C0603C104K5RACTU") (field (name "TOLERANCE") " ±10%"))
      (libsource (lib "eagle-import") (part "C100NFC0603"))
    )
    (comp (ref "C21")
      (value "220nF")
      (footprint "eagle-import:C0603")
      (fields (field (name "MPN") "C0603C224K3RACTU") (field (name "TOLERANCE") "±10%"))
      (libsource (lib "eagle-import") (part "C0603C224K3RACTU"))
    )
    (comp (ref "C23")
      (value "100nF")
      (footprint "eagle-import:C0603")
      (fields (field (name "MPN") "C0603C104K5RACTU") (field (name "TOLERANCE") " ±10%"))
      (libsource (lib "eagle-import") (part "C100NFC0603"))
    )
    (comp (ref "C60")
      (value "220nF")
      (footprint "eagle-import:C0603")
      (fields (field (name "MPN") "C0603C224K3RACTU") (field (name "TOLERANCE") "±10%"))
      (libsource (lib "eagle-import") (part "C0603C224K3RACTU"))
    )
    (comp (ref "C80")
      (value "100nF")
      (footprint "eagle-import:C0603")
      (fields (field (name "MPN") "C0603C104K5RACTU") (field (name "TOLERANCE") " ±10%"))
      (libsource (lib "eagle-import") (part "C100NFC0603"))
    )
    (comp (ref "C81")
      (value "10uF")
      (footprint "eagle-import:C0603")
      (fields (field (name "MPN") "C0603C106M9PACTU") (field (name "TOLERANCE") "±20%"))
      (libsource (lib "eagle-import") (part "C0603C106M9PACTU"))
    )
    (comp (ref "C82")
      (value "100nF")
      (footprint "eagle-import:C0603")
      (fields (field (name "MPN") "C0603C104K5RACTU") (field (name "TOLERANCE") " ±10%"))
      (libsource (lib "eagle-import") (part "C100NFC0603"))
    )
    (comp (ref "C83")
      (value "220nF")
      (footprint "eagle-import:C0603")
      (fields (field (name "MPN") "C0603C224K3RACTU") (field (name "TOLERANCE") "±10%"))
      (libsource (lib "eagle-import") (part "C0603C224K3RACTU"))
    )
    (comp (ref "C85")
      (value "220nF")
      (footprint "eagle-import:C0603")
      (fields (field (name "MPN") "C0603C224K3RACTU") (field (name "TOLERANCE") "±10%"))
      (libsource (lib "eagle-import") (part "C0603C224K3RACTU"))
    )
    (comp (ref "C86")
      (value "100nF")
      (footprint "eagle-import:C0603")
      (fields (field (name "MPN") "C0603C104K5RACTU") (field (name "TOLERANCE") " ±10%"))
      (libsource (lib "eagle-import") (part "C100NFC0603"))
    )
    (comp (ref "R5")
      (value "180k")
      (footprint "eagle-import:R0603")
      (fields (field (name "OC_NEWARK") "unknown"))
      (libsource (lib "eagle-import") (part "R180KR0603"))
    )
    (comp (ref "R6")
      (value "180k")
      (footprint "eagle-import:R0603")
      (fields (field (name "OC_NEWARK") "unknown"))
      (libsource (lib "eagle-import") (part "R180KR0603"))
    )
    (comp (ref "R7")
      (value "10K")
      (footprint "eagle-import:R0603")
      (fields (field (name "OC_NEWARK") "unknown"))
      (libsource (lib "eagle-import") (part "R10KR0603"))
    )
    (comp (ref "R8")
      (value "10K")
      (footprint "eagle-import:R0603")
      (fields (field (name "OC_NEWARK") "unknown"))
      (libsource (lib "eagle-import") (part "R10KR0603"))
    )
    (comp (ref "R9")
      (value "100k")
      (footprint "eagle-import:R0603")
      (description "100k Ohm ±1% 0.1W, 1/10W Chip Resistor 0603")
      (fields (field (name "OC_NEWARK") "unknown"))
      (libsource (lib "eagle-import") (part "R100KR0603"))
    )
    (comp (ref "R10")
      (value "100k")
      (footprint "eagle-import:R0603")
      (description "100k Ohm ±1% 0.1W, 1/10W Chip Resistor 0603")
      (fields (field (name "OC_NEWARK") "unknown"))
      (libsource (lib "eagle-import") (part "R100KR0603"))
    )
    (comp (ref "R11")
      (value "100k")
      (footprint "eagle-import:R0603")
      (description "100k Ohm ±1% 0.1W, 1/10W Chip Resistor 0603")
      (fields (field (name "OC_NEWARK") "unknown"))
      (libsource (lib "eagle-import") (part "R100KR0603"))
    )
    (comp (ref "R12")
      (value "10M")
      (footprint "eagle-import:R0603")
      (fields (field (name "OC_NEWARK") "unknown"))
      (libsource (lib "eagle-import") (part "R10MR0603"))
    )
    (comp (ref "R13")
      (value "10M")
      (footprint "eagle-import:R0603")
      (fields (field (name "OC_EC") "CRCW060310M0FKEA"))
      (libsource (lib "eagle-import") (part "R10MR0603"))
    )
    (comp (ref "R14")
      (value "3K3")
      (footprint "eagle-import:R0603")
      (fields (field (name "OC_NEWARK") "unknown"))
      (libsource (lib "eagle-import") (part "R3K3R0603"))
    )
    (comp (ref "R15")
      (value "180k")
      (footprint "eagle-import:R0603")
      (fields (field (name "OC_NEWARK") "unknown"))
      (libsource (lib "eagle-import") (part "R180KR0603"))
    )
    (comp (ref "R16")
      (value "10M")
      (footprint "eagle-import:R0603")
      (fields (field (name "OC_NEWARK") "unknown"))
      (libsource (lib "eagle-import") (part "R10MR0603"))
    )
    (comp (ref "R17")
      (value "10M")
      (footprint "eagle-import:R0603")
      (fields (field (name "OC_NEWARK") "unknown"))
      (libsource (lib "eagle-import") (part "R10MR0603"))
    )
    (comp (ref "R18")
      (value "499k")
      (footprint "eagle-import:R0603")
      (fields
        (field (name "MPN") "CRCW0201499KFKED")
        (field (name "MPN_1") "CRCW0201499KFKED")
        (field (name "OC_NEWARK") "01X2013")
      )
      (libsource (lib "eagle-import") (part "R499KR0603"))
    )
    (comp (ref "R20")
      (value "180k")
      (footprint "eagle-import:R0603")
      (fields (field (name "OC_NEWARK") "unknown"))
      (libsource (lib "eagle-import") (part "R180KR0603"))
    )
    (comp (ref "R22")
      (value "10M")
      (footprint "eagle-import:R0603")
      (fields (field (name "OC_NEWARK") "unknown"))
      (libsource (lib "eagle-import") (part "R10MR0603"))
    )
    (comp (ref "R43")
      (value "10M")
      (footprint "eagle-import:R0603")
      (fields (field (name "OC_NEWARK") "unknown"))
      (libsource (lib "eagle-import") (part "R10MR0603"))
    )
    (comp (ref "R46")
      (value "10M")
      (footprint "eagle-import:R0603")
      (fields (field (name "OC_NEWARK") "unknown"))
      (libsource (lib "eagle-import") (part "R10MR0603"))
    )
    (comp (ref "R61")
      (value "10K")
      (footprint "eagle-import:R0603")
      (fields (field (name "OC_NEWARK") "unknown"))
      (libsource (lib "eagle-import") (part "R10KR0603"))
    )
    (comp (ref "R67")
      (value "10K")
      (footprint "eagle-import:R0603")
      (fields (field (name "OC_NEWARK") "unknown"))
      (libsource (lib "eagle-import") (part "R10KR0603"))
    )
    (comp (ref "R70")
      (value "100k")
      (footprint "eagle-import:R0603")
      (description "100k Ohm ±1% 0.1W, 1/10W Chip Resistor 0603")
      (fields (field (name "OC_NEWARK") "unknown"))
      (libsource (lib "eagle-import") (part "R100KR0603"))
    )
    (comp (ref "R71")
      (value "100k")
      (footprint "eagle-import:R0603")
      (description "100k Ohm ±1% 0.1W, 1/10W Chip Resistor 0603")
      (fields (field (name "OC_NEWARK") "unknown"))
      (libsource (lib "eagle-import") (part "R100KR0603"))
    )
    (comp (ref "R72")
      (value "100k")
      (footprint "eagle-import:R0603")
      (description "100k Ohm ±1% 0.1W, 1/10W Chip Resistor 0603")
      (fields (field (name "OC_NEWARK") "unknown"))
      (libsource (lib "eagle-import") (part "R100KR0603"))
    )
    (comp (ref "R73")
      (value "3K3")
      (footprint "eagle-import:R0603")
      (fields (field (name "OC_NEWARK") "unknown"))
      (libsource (lib "eagle-import") (part "R3K3R0603"))
    )
    (comp (ref "R77")
      (value "10M")
      (footprint "eagle-import:R0603")
      (fields (field (name "OC_NEWARK") "unknown"))
      (libsource (lib "eagle-import") (part "R10MR0603"))
    )
    (comp (ref "R92")
      (value "NM")
      (footprint "eagle-import:R0603")
      (libsource (lib "eagle-import") (part "RESISTOR0603-RES"))
    )
    (comp (ref "R93")
      (value "10K")
      (footprint "eagle-import:R0603")
      (description "10k Ohm ±1% 0.1W, 1/10W Chip Resistor 0603")
      (fields (field (name "OC_NEWARK") "unknown"))
      (libsource (lib "eagle-import") (part "R10KR0603"))
    )
    (comp (ref "TP14")
      (value "NM")
      (footprint "eagle-import:B1,27")
      (libsource (lib "eagle-import") (part "TPB1,27"))
    )
    (comp (ref "TP15")
      (value "NM")
      (footprint "eagle-import:B1,27")
      (libsource (lib "eagle-import") (part "TPB1,27"))
    )
    (comp (ref "U4")
      (value "AD8232")
      (footprint "eagle-import:LFCSP_20")
      (fields (field (name "MPN") "AD8232ACPZ-R7"))
      (libsource (lib "eagle-import") (part "AD8232"))
    )
    (comp (ref "U18")
      (value "AD8232")
      (footprint "eagle-import:LFCSP_20")
      (fields (field (name "MPN") "AD8232ACPZ-R7"))
      (libsource (lib "eagle-import") (part "AD8232"))
    )
    (comp (ref "C19")
      (value "100nF")
      (footprint "eagle-import:C0603")
      (fields (field (name "MPN") "C0603C104K5RACTU") (field (name "TOLERANCE") " ±10%"))
      (libsource (lib "eagle-import") (part "C100NFC0603"))
    )
    (comp (ref "C24")
      (value "100nF")
      (footprint "eagle-import:C0603")
      (fields (field (name "MPN") "C0603C104K5RACTU") (field (name "TOLERANCE") " ±10%"))
      (libsource (lib "eagle-import") (part "C100NFC0603"))
    )
    (comp (ref "C26")
      (value "470nF")
      (footprint "eagle-import:C0603")
      (fields (field (name "MPN") "C0603C474K4RACTU") (field (name "TOLERANCE") "±10%"))
      (libsource (lib "eagle-import") (part "C0603C474K4RACTU"))
    )
    (comp (ref "C27")
      (value "470nF")
      (footprint "eagle-import:C0603")
      (fields (field (name "MPN") "C0603C474K4RACTU") (field (name "TOLERANCE") "±10%"))
      (libsource (lib "eagle-import") (part "C0603C474K4RACTU"))
    )
    (comp (ref "C28")
      (value "100nF")
      (footprint "eagle-import:C0603")
      (fields (field (name "MPN") "C0603C104K5RACTU") (field (name "TOLERANCE") " ±10%"))
      (libsource (lib "eagle-import") (part "C100NFC0603"))
    )
    (comp (ref "C30")
      (value "10uF")
      (footprint "eagle-import:C0603")
      (fields (field (name "MPN") "C0603C106M9PACTU") (field (name "TOLERANCE") "±20%"))
      (libsource (lib "eagle-import") (part "C0603C106M9PACTU"))
    )
    (comp (ref "C31")
      (value "100nF")
      (footprint "eagle-import:C0603")
      (fields (field (name "MPN") "C0603C104K5RACTU") (field (name "TOLERANCE") " ±10%"))
      (libsource (lib "eagle-import") (part "C100NFC0603"))
    )
    (comp (ref "C32")
      (value "10pF")
      (footprint "eagle-import:C0603")
      (fields (field (name "MPN") "C0603C100J5GACTU") (field (name "TOLERANCE") "±5%"))
      (libsource (lib "eagle-import") (part "C0603C100J5GACTU"))
    )
    (comp (ref "C33")
      (value "10pF")
      (footprint "eagle-import:C0603")
      (fields (field (name "MPN") "C0603C100J5GACTU") (field (name "TOLERANCE") "±5%"))
      (libsource (lib "eagle-import") (part "C0603C100J5GACTU"))
    )
    (comp (ref "C34")
      (value "470nF")
      (footprint "eagle-import:C0603")
      (fields (field (name "MPN") "C0603C474K4RACTU") (field (name "TOLERANCE") "±10%"))
      (libsource (lib "eagle-import") (part "C0603C474K4RACTU"))
    )
    (comp (ref "C48")
      (value "100nF")
      (footprint "eagle-import:C0603")
      (fields (field (name "MPN") "C0603C104K5RACTU") (field (name "TOLERANCE") " ±10%"))
      (libsource (lib "eagle-import") (part "C100NFC0603"))
    )
    (comp (ref "C52")
      (value "10uF")
      (footprint "eagle-import:C0603")
      (fields (field (name "MPN") "C0603C106M9PACTU") (field (name "TOLERANCE") "±20%"))
      (libsource (lib "eagle-import") (part "C0603C106M9PACTU"))
    )
    (comp (ref "C53")
      (value "100nF")
      (footprint "eagle-import:C0603")
      (fields (field (name "MPN") "C0603C104K5RACTU") (field (name "TOLERANCE") " ±10%"))
      (libsource (lib "eagle-import") (part "C100NFC0603"))
    )
    (comp (ref "C54")
      (value "10uF")
      (footprint "eagle-import:C0603")
      (fields (field (name "MPN") "C0603C106M9PACTU") (field (name "TOLERANCE") "±20%"))
      (libsource (lib "eagle-import") (part "C0603C106M9PACTU"))
    )
    (comp (ref "CE")
      (value "NM")
      (footprint "eagle-import:TH0305")
      (libsource (lib "eagle-import") (part "TPLM"))
    )
    (comp (ref "CK")
      (value "NM")
      (footprint "eagle-import:TH0305")
      (libsource (lib "eagle-import") (part "TPLM"))
    )
    (comp (ref "IC1")
      (value "OPA340N")
      (footprint "eagle-import:SOT23-5")
      (fields (field (name "MPN") "OPA340NA/3KG4") (field (name "MPN_1") "OPA340NA/3K"))
      (libsource (lib "eagle-import") (part "OPA340N"))
    )
    (comp (ref "R19")
      (value "470R")
      (footprint "eagle-import:R0603")
      (fields (field (name "MPN") "ERJ3EKF4700V"))
      (libsource (lib "eagle-import") (part "RESISTOR0603-RES"))
    )
    (comp (ref "R21")
      (value "10K")
      (footprint "eagle-import:R0603")
      (fields (field (name "OC_NEWARK") "unknown"))
      (libsource (lib "eagle-import") (part "R10KR0603"))
    )
    (comp (ref "R24")
      (value "100k")
      (footprint "eagle-import:R0603")
      (description "100k Ohm ±1% 0.1W, 1/10W Chip Resistor 0603")
      (fields (field (name "OC_NEWARK") "unknown"))
      (libsource (lib "eagle-import") (part "R100KR0603"))
    )
    (comp (ref "R26")
      (value "N.M. (150k)")
      (footprint "eagle-import:R0603")
      (libsource (lib "eagle-import") (part "RESISTOR0603-RES"))
    )
    (comp (ref "R51")
      (value "820R")
      (footprint "eagle-import:R0603")
      (fields (field (name "OC_NEWARK") "unknown"))
      (libsource (lib "eagle-import") (part "R820RR0603"))
    )
    (comp (ref "R58")
      (value "820R")
      (footprint "eagle-import:R0603")
      (fields (field (name "OC_NEWARK") "unknown"))
      (libsource (lib "eagle-import") (part "R820RR0603"))
    )
    (comp (ref "R83")
      (value "820R")
      (footprint "eagle-import:R0603")
      (fields (field (name "OC_NEWARK") "unknown"))
      (libsource (lib "eagle-import") (part "R820RR0603"))
    )
    (comp (ref "R84")
      (value "820R")
      (footprint "eagle-import:R0603")
      (fields (field (name "OC_NEWARK") "unknown"))
      (libsource (lib "eagle-import") (part "R820RR0603"))
    )
    (comp (ref "R89")
      (value "10K")
      (footprint "eagle-import:R0603")
      (fields (field (name "OC_NEWARK") "unknown"))
      (libsource (lib "eagle-import") (part "R10KR0603"))
    )
    (comp (ref "SI")
      (value "NM")
      (footprint "eagle-import:TH0305")
      (libsource (lib "eagle-import") (part "TPLM"))
    )
    (comp (ref "SO")
      (value "NM")
      (footprint "eagle-import:TH0305")
      (libsource (lib "eagle-import") (part "TPLM"))
    )
    (comp (ref "TP1")
      (value "NM")
      (footprint "eagle-import:TH0305")
      (libsource (lib "eagle-import") (part "TPLM"))
    )
    (comp (ref "TP2")
      (value "NM")
      (footprint "eagle-import:TH0305")
      (libsource (lib "eagle-import") (part "TPLM"))
    )
    (comp (ref "TP3")
      (value "NM")
      (footprint "eagle-import:TH0305")
      (libsource (lib "eagle-import") (part "TPLM"))
    )
    (comp (ref "TP4")
      (value "NM")
      (footprint "eagle-import:TH0305")
      (libsource (lib "eagle-import") (part "TPLM"))
    )
    (comp (ref "TP5")
      (value "NM")
      (footprint "eagle-import:TH0305")
      (libsource (lib "eagle-import") (part "TPLM"))
    )
    (comp (ref "TP21")
      (value "NM")
      (footprint "eagle-import:TH0305")
      (libsource (lib "eagle-import") (part "TPLM"))
    )
    (comp (ref "TP22")
      (value "NM")
      (footprint "eagle-import:TH0305")
      (libsource (lib "eagle-import") (part "TPLM"))
    )
    (comp (ref "U5")
      (value "ADUCM360BCPZ128")
      (footprint "eagle-import:LFCSP48")
      (libsource (lib "eagle-import") (part "ADUCM360BCPZ128"))
    )
    (comp (ref "X1")
      (value "ABS05-32.768KHZ")
      (footprint "eagle-import:CRYSTAL-2PIN")
      (fields (field (name "MPN") "ABS05-32.768KHZ-T"))
      (libsource (lib "eagle-import") (part "ABS05-32.768KHZ-T2PIN"))
    )
    (comp (ref "X4")
      (value "MICROMATCH-8")
      (footprint "eagle-import:MICROMATCH-8")
      (fields (field (name "MF") "FARNELL") (field (name "MPN") "7-215464-8"))
      (libsource (lib "eagle-import") (part "MICROMATCH-8"))
    )
    (comp (ref "X6")
      (value "MICROMATCH-20")
      (footprint "eagle-import:MICROMATCH-20")
      (fields
        (field (name "MPN") "TE Part # 9-215079-0")
        (field (name "MPN_1") "2-215079-0")
        (field (name "OC_NEWARK") "17R7376")
      )
      (libsource (lib "eagle-import") (part "MICROMATCH-20"))
    )
    (comp (ref "X7")
      (value "nm")
      (footprint "eagle-import:MICROMATCH-20")
      (fields (field (name "MPN") "TE Part # 9-215079-0") (field (name "OC_NEWARK") "unknown"))
      (libsource (lib "eagle-import") (part "MICROMATCH-20"))
    )
    (comp (ref "X9")
      (value "NM")
      (footprint "eagle-import:70543-14")
      (libsource (lib "eagle-import") (part "C-GRID-14-70543"))
    )
    (comp (ref "C1U15")
      (value "100nF")
      (footprint "eagle-import:C0603")
      (fields (field (name "MPN") "C0603C104K5RACTU") (field (name "TOLERANCE") " ±10%"))
      (libsource (lib "eagle-import") (part "C100NFC0603"))
    )
    (comp (ref "C1U16")
      (value "100nF")
      (footprint "eagle-import:C0603")
      (fields (field (name "MPN") "C0603C104K5RACTU") (field (name "TOLERANCE") " ±10%"))
      (libsource (lib "eagle-import") (part "C100NFC0603"))
    )
    (comp (ref "C2U15")
      (value "100nF")
      (footprint "eagle-import:C0603")
      (fields (field (name "MPN") "C0603C104K5RACTU") (field (name "TOLERANCE") " ±10%"))
      (libsource (lib "eagle-import") (part "C100NFC0603"))
    )
    (comp (ref "C2U16")
      (value "100nF")
      (footprint "eagle-import:C0603")
      (fields (field (name "MPN") "C0603C104K5RACTU") (field (name "TOLERANCE") " ±10%"))
      (libsource (lib "eagle-import") (part "C100NFC0603"))
    )
    (comp (ref "C44")
      (value "100nF")
      (footprint "eagle-import:1206")
      (fields
        (field (name "MPN") "12062C104KAT2A")
        (field (name "TOLERANCE") "±10%")
        (field (name "VOLTAGERATING") "200V")
      )
      (libsource (lib "eagle-import") (part "12062C104KAT2A"))
    )
    (comp (ref "C45")
      (value "100nF")
      (footprint "eagle-import:C0603")
      (fields (field (name "MPN") "C0603C104K5RACTU") (field (name "TOLERANCE") " ±10%"))
      (libsource (lib "eagle-import") (part "C100NFC0603"))
    )
    (comp (ref "C46")
      (value "2u2")
      (footprint "eagle-import:C2220K")
      (fields
        (field (name "MPN") "CGA9P3X7T2E225K250KA")
        (field (name "TOLERANCE") "±10%")
        (field (name "VOLTAGERATING") "250V")
        (field (name "MPN_1") "ECA-2GHG2R2")
      )
      (libsource (lib "eagle-import") (part "CGA9P3X7T2E225K250KA"))
    )
    (comp (ref "C49")
      (value "100nF")
      (footprint "eagle-import:C0603")
      (fields (field (name "MPN") "C0603C104K5RACTU") (field (name "TOLERANCE") " ±10%"))
      (libsource (lib "eagle-import") (part "C100NFC0603"))
    )
    (comp (ref "C50")
      (value "100nF")
      (footprint "eagle-import:1206")
      (fields
        (field (name "MPN") "12062C104KAT2A")
        (field (name "TOLERANCE") "±10%")
        (field (name "VOLTAGERATING") "200V")
      )
      (libsource (lib "eagle-import") (part "12062C104KAT2A"))
    )
    (comp (ref "C51")
      (value "2u2")
      (footprint "eagle-import:C2220K")
      (fields
        (field (name "MPN") "CGA9P3X7T2E225K250KA")
        (field (name "TOLERANCE") "±10%")
        (field (name "VOLTAGERATING") "250V")
        (field (name "MPN_1") "ECA-2GHG2R2")
      )
      (libsource (lib "eagle-import") (part "CGA9P3X7T2E225K250KA"))
    )
    (comp (ref "C67")
      (value "100nF")
      (footprint "eagle-import:C0603")
      (fields (field (name "MPN") "C0603C104K5RACTU") (field (name "TOLERANCE") " ±10%"))
      (libsource (lib "eagle-import") (part "C100NFC0603"))
    )
    (comp (ref "C69")
      (value "2u2")
      (footprint "eagle-import:C2220K")
      (fields
        (field (name "MPN") "CGA9P3X7T2E225K250KA")
        (field (name "TOLERANCE") "±10%")
        (field (name "VOLTAGERATING") "250V")
        (field (name "MPN_1") "ECA-2GHG2R2")
      )
      (libsource (lib "eagle-import") (part "CGA9P3X7T2E225K250KA"))
    )
    (comp (ref "C70")
      (value "2u2")
      (footprint "eagle-import:C2220K")
      (fields
        (field (name "MPN") "CGA9P3X7T2E225K250KA")
        (field (name "TOLERANCE") "±10%")
        (field (name "VOLTAGERATING") "250V")
        (field (name "MPN_1") "ECA-2GHG2R2")
      )
      (libsource (lib "eagle-import") (part "CGA9P3X7T2E225K250KA"))
    )
    (comp (ref "C75")
      (value "100PF")
      (footprint "eagle-import:C0603")
      (fields
        (field (name "MPN") "0603YC101KAT4A")
        (field (name "TOLERANCE") "±10%")
        (field (name "OC_NEWARK") "unknown")
      )
      (libsource (lib "eagle-import") (part "0603YC101KAT4A"))
    )
    (comp (ref "C76")
      (value "100PF")
      (footprint "eagle-import:C0603")
      (fields
        (field (name "MPN") "0603YC101KAT4A")
        (field (name "TOLERANCE") "±10%")
        (field (name "OC_NEWARK") "unknown")
      )
      (libsource (lib "eagle-import") (part "0603YC101KAT4A"))
    )
    (comp (ref "C144")
      (value "100nF")
      (footprint "eagle-import:C0603")
      (fields (field (name "MPN") "C0603C104K5RACTU") (field (name "TOLERANCE") " ±10%"))
      (libsource (lib "eagle-import") (part "C100NFC0603"))
    )
    (comp (ref "CU17")
      (value "100nF")
      (footprint "eagle-import:C0603")
      (fields (field (name "MPN") "C0603C104K5RACTU") (field (name "TOLERANCE") " ±10%"))
      (libsource (lib "eagle-import") (part "C100NFC0603"))
    )
    (comp (ref "D2")
      (value "BAS40-04W")
      (footprint "eagle-import:SOT323")
      (fields (field (name "MPN") "NXP:BAS40-04W") (field (name "MPN_1") "BAS40-04W 115."))
      (libsource (lib "eagle-import") (part "BAS40-04W115"))
    )
    (comp (ref "D6N")
      (value "BAV3004W-7-F")
      (footprint "eagle-import:SOD123")
      (libsource (lib "eagle-import") (part "BAV3004W-7-F"))
    )
    (comp (ref "D6P")
      (value "BAV3004W-7-F")
      (footprint "eagle-import:SOD123")
      (libsource (lib "eagle-import") (part "BAV3004W-7-F"))
    )
    (comp (ref "D6P1")
      (value "BAV3004W-7-F")
      (footprint "eagle-import:SOD123")
      (libsource (lib "eagle-import") (part "BAV3004W-7-F"))
    )
    (comp (ref "D6P2")
      (value "BAV3004W-7-F")
      (footprint "eagle-import:SOD123")
      (libsource (lib "eagle-import") (part "BAV3004W-7-F"))
    )
    (comp (ref "D8")
      (value "BAS40-04W")
      (footprint "eagle-import:SOT323")
      (fields (field (name "MPN") "NXP:BAS40-04W") (field (name "MPN_1") "BAS40-04W 115."))
      (libsource (lib "eagle-import") (part "BAS40-04W115"))
    )
    (comp (ref "D12")
      (value "BAS40-04W")
      (footprint "eagle-import:SOT323")
      (fields (field (name "MPN") "NXP:BAS40-04W") (field (name "MPN_1") "BAS40-04W 115."))
      (libsource (lib "eagle-import") (part "BAS40-04W115"))
    )
    (comp (ref "D22")
      (value "BAS40-04W")
      (footprint "eagle-import:SOT323")
      (fields (field (name "MPN") "NXP:BAS40-04W") (field (name "MPN_1") "BAS40-04W 115."))
      (libsource (lib "eagle-import") (part "BAS40-04W115"))
    )
    (comp (ref "L11")
      (value "47uH")
      (footprint "eagle-import:1206")
      (fields (field (name "MPN") "LQH31MN470K03L "))
      (libsource (lib "eagle-import") (part "LQH31MN470K03L"))
    )
    (comp (ref "L12")
      (value "47uH")
      (footprint "eagle-import:1206")
      (fields (field (name "MPN") "LQH31MN470K03L "))
      (libsource (lib "eagle-import") (part "LQH31MN470K03L"))
    )
    (comp (ref "R29")
      (value "1k")
      (footprint "eagle-import:R0603")
      (libsource (lib "eagle-import") (part "R1KR0603"))
    )
    (comp (ref "R40")
      (value "1M")
      (footprint "eagle-import:R0603")
      (fields (field (name "OC_NEWARK") "unknown"))
      (libsource (lib "eagle-import") (part "R1MR0603"))
    )
    (comp (ref "R41")
      (value "1k")
      (footprint "eagle-import:R0603")
      (libsource (lib "eagle-import") (part "R1KR0603"))
    )
    (comp (ref "R42")
      (value "1M")
      (footprint "eagle-import:R0603")
      (fields (field (name "OC_NEWARK") "unknown"))
      (libsource (lib "eagle-import") (part "R1MR0603"))
    )
    (comp (ref "R48")
      (value "10R")
      (footprint "eagle-import:R0603")
      (description "0603, Res 10.0Ohm, 50V, 1.0%, 100mW")
      (libsource (lib "eagle-import") (part "RESISTOR0603-RES"))
    )
    (comp (ref "R49")
      (value "10R")
      (footprint "eagle-import:R0603")
      (description "0603, Res 10.0Ohm, 50V, 1.0%, 100mW")
      (libsource (lib "eagle-import") (part "RESISTOR0603-RES"))
    )
    (comp (ref "R55")
      (value "1k")
      (footprint "eagle-import:R0603")
      (libsource (lib "eagle-import") (part "R1KR0603"))
    )
    (comp (ref "R56")
      (value "100k")
      (footprint "eagle-import:R0603")
      (description "100k Ohm ±1% 0.1W, 1/10W Chip Resistor 0603")
      (fields (field (name "OC_NEWARK") "unknown"))
      (libsource (lib "eagle-import") (part "R100KR0603"))
    )
    (comp (ref "R57")
      (value "100k")
      (footprint "eagle-import:R0603")
      (description "100k Ohm ±1% 0.1W, 1/10W Chip Resistor 0603")
      (fields (field (name "OC_NEWARK") "unknown"))
      (libsource (lib "eagle-import") (part "R100KR0603"))
    )
    (comp (ref "R62")
      (value "1M")
      (footprint "eagle-import:R0603")
      (fields (field (name "OC_NEWARK") "unknown"))
      (libsource (lib "eagle-import") (part "R1MR0603"))
    )
    (comp (ref "R63")
      (value "1k")
      (footprint "eagle-import:R0603")
      (libsource (lib "eagle-import") (part "R1KR0603"))
    )
    (comp (ref "R64")
      (value "4k7")
      (footprint "eagle-import:R0603")
      (fields (field (name "OC_NEWARK") "unknown"))
      (libsource (lib "eagle-import") (part "R4K7R0603"))
    )
    (comp (ref "R65")
      (value "100k")
      (footprint "eagle-import:R0603")
      (description "100k Ohm ±1% 0.1W, 1/10W Chip Resistor 0603")
      (fields (field (name "OC_NEWARK") "unknown"))
      (libsource (lib "eagle-import") (part "R100KR0603"))
    )
    (comp (ref "R66")
      (value "390R")
      (footprint "eagle-import:R0603")
      (fields (field (name "OC_NEWARK") "unknown"))
      (libsource (lib "eagle-import") (part "R390RR0603"))
    )
    (comp (ref "R68")
      (value "100k")
      (footprint "eagle-import:R0603")
      (description "100k Ohm ±1% 0.1W, 1/10W Chip Resistor 0603")
      (fields (field (name "OC_NEWARK") "unknown"))
      (libsource (lib "eagle-import") (part "R100KR0603"))
    )
    (comp (ref "R69")
      (value "100k")
      (footprint "eagle-import:R0603")
      (description "100k Ohm ±1% 0.1W, 1/10W Chip Resistor 0603")
      (fields (field (name "OC_NEWARK") "unknown"))
      (libsource (lib "eagle-import") (part "R100KR0603"))
    )
    (comp (ref "R80")
      (value "1k")
      (footprint "eagle-import:R0603")
      (libsource (lib "eagle-import") (part "R1KR0603"))
    )
    (comp (ref "R144")
      (value "10M")
      (footprint "eagle-import:R0603")
      (fields (field (name "OC_NEWARK") "unknown"))
      (libsource (lib "eagle-import") (part "R10MR0603"))
    )
    (comp (ref "R145")
      (value "10M")
      (footprint "eagle-import:R0603")
      (fields (field (name "OC_NEWARK") "unknown"))
      (libsource (lib "eagle-import") (part "R10MR0603"))
    )
    (comp (ref "RL7")
      (value "AQY210S")
      (footprint "eagle-import:SOP04")
      (fields (field (name "MPN") "AQY210SX"))
      (libsource (lib "eagle-import") (part "AQY210S"))
    )
    (comp (ref "RL8")
      (value "AQY210S")
      (footprint "eagle-import:SOP04")
      (fields (field (name "MPN") "AQY210SX"))
      (libsource (lib "eagle-import") (part "AQY210S"))
    )
    (comp (ref "RSENSE")
      (value "20R")
      (footprint "eagle-import:R2010")
      (fields (field (name "OC_NEWARK") "unknown"))
      (libsource (lib "eagle-import") (part "R20RR2010"))
    )
    (comp (ref "T4")
      (value "ZVN4525ZTA")
      (footprint "eagle-import:SOT89")
      (libsource (lib "eagle-import") (part "ZVN4525ZTA"))
    )
    (comp (ref "T25")
      (value "ZVP4525ZTA")
      (footprint "eagle-import:SOT89")
      (libsource (lib "eagle-import") (part "ZVP4525ZTA"))
    )
    (comp (ref "TP16")
      (value "NM")
      (footprint "eagle-import:TH0305")
      (libsource (lib "eagle-import") (part "TPLM"))
    )
    (comp (ref "TP17")
      (value "NM")
      (footprint "eagle-import:TH0305")
      (libsource (lib "eagle-import") (part "TPLM"))
    )
    (comp (ref "TP20")
      (value "NM")
      (footprint "eagle-import:TH0305")
      (libsource (lib "eagle-import") (part "TPLM"))
    )
    (comp (ref "U15")
      (value "AD8642ARMZ")
      (footprint "eagle-import:MSOP8")
      (fields (field (name "OC_NEWARK") "23X6319"))
      (libsource (lib "eagle-import") (part "AD8642ARMZ"))
    )
    (comp (ref "U16")
      (value "AD8642ARMZ")
      (footprint "eagle-import:MSOP8")
      (fields (field (name "OC_NEWARK") "23X6319"))
      (libsource (lib "eagle-import") (part "AD8642ARMZ"))
    )
    (comp (ref "U17")
      (value "AD8642ARMZ")
      (footprint "eagle-import:MSOP8")
      (fields (field (name "OC_NEWARK") "23X6319"))
      (libsource (lib "eagle-import") (part "AD8642ARMZ"))
    )
  )
  (nets
    (net (code "1") (name "+3V3") (class "Default")
      (node (ref "C19") (pin "1") (pinfunction "C1_1") (pintype "passive"))
      (node (ref "C24") (pin "1") (pinfunction "C1_1") (pintype "passive"))
      (node (ref "C28") (pin "1") (pinfunction "C1_1") (pintype "passive"))
      (node (ref "C29") (pin "2") (pinfunction "C2_2") (pintype "passive"))
      (node (ref "C41") (pin "1") (pinfunction "C1_1") (pintype "passive"))
      (node (ref "C48") (pin "1") (pinfunction "C1_1") (pintype "passive"))
      (node (ref "C52") (pin "2") (pinfunction "C2_2") (pintype "passive"))
      (node (ref "IC1") (pin "5") (pinfunction "V+_5") (pintype "power_in"))
      (node (ref "L5") (pin "2") (pinfunction "2_2") (pintype "bidirectional"))
      (node (ref "R24") (pin "2") (pinfunction "2_2") (pintype "passive"))
      (node (ref "R89") (pin "1") (pinfunction "1_1") (pintype "passive"))
      (node (ref "R90") (pin "2") (pinfunction "2_2") (pintype "passive"))
      (node (ref "U13") (pin "3") (pinfunction "VIN_3") (pintype "bidirectional"))
      (node (ref "U5") (pin "37") (pinfunction "IOVDD0_37") (pintype "bidirectional"))
      (node (ref "U5") (pin "6") (pinfunction "IOVDD_6") (pintype "bidirectional"))
      (node (ref "X4") (pin "1") (pinfunction "S_1") (pintype "passive"))
      (node (ref "X6") (pin "13") (pinfunction "S_13") (pintype "passive"))
    )
    (net (code "2") (name "+3V3_AN") (class "Default")
      (node (ref "C16") (pin "2") (pinfunction "C2_2") (pintype "passive"))
      (node (ref "C20") (pin "1") (pinfunction "C1_1") (pintype "passive"))
      (node (ref "C30") (pin "2") (pinfunction "C2_2") (pintype "passive"))
      (node (ref "C31") (pin "1") (pinfunction "C1_1") (pintype "passive"))
      (node (ref "C59") (pin "2") (pinfunction "C2_2") (pintype "passive"))
      (node (ref "C81") (pin "2") (pinfunction "C2_2") (pintype "passive"))
      (node (ref "C82") (pin "1") (pinfunction "C1_1") (pintype "passive"))
      (node (ref "L4") (pin "2") (pinfunction "2_2") (pintype "bidirectional"))
      (node (ref "R17") (pin "2") (pinfunction "2_2") (pintype "passive"))
      (node (ref "R93") (pin "2") (pinfunction "2_2") (pintype "passive"))
      (node (ref "U18") (pin "13") (pinfunction "~{SDN}_13") (pintype "bidirectional"))
      (node (ref "U18") (pin "14") (pinfunction "AC/~{DC}_14") (pintype "bidirectional"))
      (node (ref "U18") (pin "17VS") (pinfunction "+VS_17VS") (pintype "bidirectional"))
      (node (ref "U4") (pin "13") (pinfunction "~{SDN}_13") (pintype "bidirectional"))
      (node (ref "U4") (pin "17VS") (pinfunction "+VS_17VS") (pintype "bidirectional"))
      (node (ref "U5") (pin "17") (pinfunction "AVDD_17") (pintype "bidirectional"))
    )
    (net (code "3") (name "3V3NEG") (class "Default")
      (node (ref "C43") (pin "1") (pinfunction "1_1") (pintype "passive"))
      (node (ref "IC17") (pin "1") (pinfunction "VOUT_1") (pintype "power_in"))
      (node (ref "L10") (pin "1") (pinfunction "1_1") (pintype "bidirectional"))
    )
    (net (code "7") (name "BUTTON") (class "Default")
      (node (ref "C90") (pin "2") (pinfunction "C2_2") (pintype "passive"))
      (node (ref "R90") (pin "1") (pinfunction "1_1") (pintype "passive"))
      (node (ref "R91") (pin "2") (pinfunction "2_2") (pintype "passive"))
      (node (ref "X6") (pin "11") (pinfunction "S_11") (pintype "passive"))
    )
    (net (code "8") (name "CHRGVCCS") (class "Default")
      (node (ref "R66") (pin "2") (pinfunction "2_2") (pintype "passive"))
      (node (ref "U5") (pin "46") (pinfunction "P2.0/SCL_46") (pintype "bidirectional"))
    )
    (net (code "9") (name "CMD_MLDP") (class "Default")
      (node (ref "TP22") (pin "TP") (pinfunction "TP_TP") (pintype "input"))
      (node (ref "U5") (pin "35") (pinfunction "P0.6/IRQ2/SIN_35") (pintype "bidirectional"))
    )
    (net (code "10") (name "COMMDRV") (class "Default")
      (node (ref "R18") (pin "2") (pinfunction "2_2") (pintype "passive"))
      (node (ref "X6") (pin "3") (pinfunction "S_3") (pintype "passive"))
    )
    (net (code "11") (name "EA1") (class "Default")
      (node (ref "R13") (pin "1") (pinfunction "1_1") (pintype "passive"))
      (node (ref "R5") (pin "1") (pinfunction "1_1") (pintype "passive"))
      (node (ref "X6") (pin "1") (pinfunction "S_1") (pintype "passive"))
    )
    (net (code "12") (name "EA2") (class "Default")
      (node (ref "R12") (pin "1") (pinfunction "1_1") (pintype "passive"))
      (node (ref "R6") (pin "1") (pinfunction "1_1") (pintype "passive"))
      (node (ref "X6") (pin "2") (pinfunction "S_2") (pintype "passive"))
    )
    (net (code "13") (name "EB1") (class "Default")
      (node (ref "R15") (pin "1") (pinfunction "1_1") (pintype "passive"))
      (node (ref "R46") (pin "1") (pinfunction "1_1") (pintype "passive"))
      (node (ref "X6") (pin "4") (pinfunction "S_4") (pintype "passive"))
    )
    (net (code "14") (name "EB2") (class "Default")
      (node (ref "R20") (pin "1") (pinfunction "1_1") (pintype "passive"))
      (node (ref "R43") (pin "1") (pinfunction "1_1") (pintype "passive"))
      (node (ref "X6") (pin "5") (pinfunction "S_5") (pintype "passive"))
    )
    (net (code "15") (name "EN_SAINV") (class "Default")
      (node (ref "R83") (pin "2") (pinfunction "2_2") (pintype "passive"))
      (node (ref "RL5") (pin "1") (pinfunction "A_1") (pintype "passive"))
      (node (ref "X9") (pin "6") (pinfunction "S_6") (pintype "passive"))
    )
    (net (code "16") (name "EN_SAPOS") (class "Default")
      (node (ref "R84") (pin "2") (pinfunction "2_2") (pintype "passive"))
      (node (ref "RL3") (pin "1") (pinfunction "A_1") (pintype "passive"))
      (node (ref "X9") (pin "5") (pinfunction "S_5") (pintype "passive"))
    )
    (net (code "17") (name "EN_SBINV") (class "Default")
      (node (ref "R51") (pin "2") (pinfunction "2_2") (pintype "passive"))
      (node (ref "RL11") (pin "1") (pinfunction "A_1") (pintype "passive"))
      (node (ref "X9") (pin "8") (pinfunction "S_8") (pintype "passive"))
    )
    (net (code "18") (name "EN_SBPOS") (class "Default")
      (node (ref "R58") (pin "2") (pinfunction "2_2") (pintype "passive"))
      (node (ref "RL9") (pin "1") (pinfunction "A_1") (pintype "passive"))
      (node (ref "X9") (pin "7") (pinfunction "S_7") (pintype "passive"))
    )
    (net (code "19") (name "EN_ST") (class "Default")
      (node (ref "TP21") (pin "TP") (pinfunction "TP_TP") (pintype "input"))
      (node (ref "U5") (pin "3") (pinfunction "P2.2/BM_3") (pintype "bidirectional"))
    )
    (net (code "20") (name "FR") (class "Default")
      (node (ref "R92") (pin "2") (pinfunction "2_2") (pintype "passive"))
      (node (ref "R93") (pin "1") (pinfunction "1_1") (pintype "passive"))
      (node (ref "U18") (pin "15") (pinfunction "FR_15") (pintype "bidirectional"))
      (node (ref "U4") (pin "15") (pinfunction "FR_15") (pintype "bidirectional"))
    )
    (net (code "21") (name "GND") (class "Default")
      (node (ref "C13") (pin "1") (pinfunction "C1_1") (pintype "passive"))
      (node (ref "C144") (pin "1") (pinfunction "C1_1") (pintype "passive"))
      (node (ref "C15") (pin "1") (pinfunction "C1_1") (pintype "passive"))
      (node (ref "C19") (pin "2") (pinfunction "C2_2") (pintype "passive"))
      (node (ref "C190") (pin "1") (pinfunction "C1_1") (pintype "passive"))
      (node (ref "C191") (pin "1") (pinfunction "C1_1") (pintype "passive"))
      (node (ref "C1U15") (pin "1") (pinfunction "C1_1") (pintype "passive"))
      (node (ref "C1U16") (pin "2") (pinfunction "C2_2") (pintype "passive"))
      (node (ref "C2") (pin "1") (pinfunction "C1_1") (pintype "passive"))
      (node (ref "C24") (pin "2") (pinfunction "C2_2") (pintype "passive"))
      (node (ref "C28") (pin "2") (pinfunction "C2_2") (pintype "passive"))
      (node (ref "C29") (pin "1") (pinfunction "C1_1") (pintype "passive"))
      (node (ref "C2U15") (pin "2") (pinfunction "C2_2") (pintype "passive"))
      (node (ref "C2U16") (pin "1") (pinfunction "C1_1") (pintype "passive"))
      (node (ref "C3") (pin "1") (pinfunction "C1_1") (pintype "passive"))
      (node (ref "C32") (pin "1") (pinfunction "C1_1") (pintype "passive"))
      (node (ref "C33") (pin "1") (pinfunction "C1_1") (pintype "passive"))
      (node (ref "C38") (pin "1") (pinfunction "C1_1") (pintype "passive"))
      (node (ref "C39") (pin "1") (pinfunction "C1_1") (pintype "passive"))
      (node (ref "C4") (pin "1") (pinfunction "C1_1") (pintype "passive"))
      (node (ref "C41") (pin "2") (pinfunction "C2_2") (pintype "passive"))
      (node (ref "C42") (pin "2") (pinfunction "C2_2") (pintype "passive"))
      (node (ref "C43") (pin "2") (pinfunction "2_2") (pintype "passive"))
      (node (ref "C44") (pin "1") (pinfunction "C1_1") (pintype "passive"))
      (node (ref "C47") (pin "2") (pinfunction "2_2") (pintype "passive"))
      (node (ref "C48") (pin "2") (pinfunction "C2_2") (pintype "passive"))
      (node (ref "C49") (pin "2") (pinfunction "C2_2") (pintype "passive"))
      (node (ref "C5") (pin "1") (pinfunction "C1_1") (pintype "passive"))
      (node (ref "C50") (pin "2") (pinfunction "C2_2") (pintype "passive"))
      (node (ref "C52") (pin "1") (pinfunction "C1_1") (pintype "passive"))
      (node (ref "C53") (pin "1") (pinfunction "C1_1") (pintype "passive"))
      (node (ref "C54") (pin "2") (pinfunction "C2_2") (pintype "passive"))
      (node (ref "C55") (pin "1") (pinfunction "1_1") (pintype "passive"))
      (node (ref "C58") (pin "1") (pinfunction "C1_1") (pintype "passive"))
      (node (ref "C6") (pin "1") (pinfunction "C1_1") (pintype "passive"))
      (node (ref "C8") (pin "1") (pinfunction "C1_1") (pintype "passive"))
      (node (ref "C88") (pin "2") (pinfunction "C2_2") (pintype "passive"))
      (node (ref "C9") (pin "1") (pinfunction "C1_1") (pintype "passive"))
      (node (ref "C90") (pin "1") (pinfunction "C1_1") (pintype "passive"))
      (node (ref "CU17") (pin "1") (pinfunction "C1_1") (pintype "passive"))
      (node (ref "D21") (pin "A") (pinfunction "1A_A") (pintype "passive"))
      (node (ref "D22") (pin "1") (pinfunction "A1_1") (pintype "passive"))
      (node (ref "D6N") (pin "C") (pinfunction "C_C") (pintype "passive"))
      (node (ref "D6P") (pin "A") (pinfunction "A_A") (pintype "passive"))
      (node (ref "D8") (pin "3") (pinfunction "C1A2_3") (pintype "passive"))
      (node (ref "IC1") (pin "2") (pinfunction "V-_2") (pintype "power_in"))
      (node (ref "IC17") (pin "4") (pinfunction "GND_4") (pintype "power_in"))
      (node (ref "PMOS1") (pin "G") (pinfunction "G_G") (pintype "bidirectional"))
      (node (ref "R2") (pin "1") (pinfunction "1_1") (pintype "passive"))
      (node (ref "R28") (pin "1") (pinfunction "1_1") (pintype "passive"))
      (node (ref "R3") (pin "1") (pinfunction "1_1") (pintype "passive"))
      (node (ref "R30") (pin "2") (pinfunction "2_2") (pintype "passive"))
      (node (ref "R62") (pin "1") (pinfunction "1_1") (pintype "passive"))
      (node (ref "RL10") (pin "2") (pinfunction "K_2") (pintype "passive"))
      (node (ref "RL12") (pin "2") (pinfunction "K_2") (pintype "passive"))
      (node (ref "RL4") (pin "2") (pinfunction "K_2") (pintype "passive"))
      (node (ref "RL6") (pin "2") (pinfunction "K_2") (pintype "passive"))
      (node (ref "RL8") (pin "2") (pinfunction "K_2") (pintype "passive"))
      (node (ref "U13") (pin "EXP") (pinfunction "GND_EXP") (pintype "bidirectional"))
      (node (ref "U17") (pin "4") (pinfunction "V-_4") (pintype "power_in"))
      (node (ref "U2") (pin "2") (pinfunction "GND_2") (pintype "passive"))
      (node (ref "U3") (pin "10") (pinfunction "PGND_10") (pintype "passive"))
      (node (ref "U3") (pin "11") (pinfunction "POWERPAD_11") (pintype "passive"))
      (node (ref "U3") (pin "5") (pinfunction "GND_5") (pintype "passive"))
      (node (ref "U3") (pin "7") (pinfunction "LBI_7") (pintype "input"))
      (node (ref "U3") (pin "8") (pinfunction "PS_8") (pintype "input"))
      (node (ref "U5") (pin "EXP") (pinfunction "EXPGND_EXP") (pintype "bidirectional"))
      (node (ref "X4") (pin "8") (pinfunction "S_8") (pintype "passive"))
      (node (ref "X6") (pin "12") (pinfunction "S_12") (pintype "passive"))
      (node (ref "X6") (pin "16") (pinfunction "S_16") (pintype "passive"))
      (node (ref "X6") (pin "8") (pinfunction "S_8") (pintype "passive"))
      (node (ref "X6") (pin "9") (pinfunction "S_9") (pintype "passive"))
      (node (ref "X7") (pin "12") (pinfunction "S_12") (pintype "passive"))
      (node (ref "X7") (pin "16") (pinfunction "S_16") (pintype "passive"))
      (node (ref "X7") (pin "8") (pinfunction "S_8") (pintype "passive"))
      (node (ref "X7") (pin "9") (pinfunction "S_9") (pintype "passive"))
      (node (ref "X9") (pin "1") (pinfunction "S_1") (pintype "passive"))
      (node (ref "X9") (pin "11") (pinfunction "S_11") (pintype "passive"))
      (node (ref "X9") (pin "14") (pinfunction "S_14") (pintype "passive"))
      (node (ref "ZD1") (pin "1C") (pinfunction "C_1C") (pintype "passive"))
      (node (ref "ZD3") (pin "2A") (pinfunction "A_2A") (pintype "passive"))
    )
    (net (code "23") (name "GNDA") (class "Default")
      (node (ref "C1") (pin "1") (pinfunction "C1_1") (pintype "passive"))
      (node (ref "C14") (pin "2") (pinfunction "C2_2") (pintype "passive"))
      (node (ref "C16") (pin "1") (pinfunction "C1_1") (pintype "passive"))
      (node (ref "C20") (pin "2") (pinfunction "C2_2") (pintype "passive"))
      (node (ref "C23") (pin "2") (pinfunction "C2_2") (pintype "passive"))
      (node (ref "C26") (pin "2") (pinfunction "C2_2") (pintype "passive"))
      (node (ref "C27") (pin "2") (pinfunction "C2_2") (pintype "passive"))
      (node (ref "C30") (pin "1") (pinfunction "C1_1") (pintype "passive"))
      (node (ref "C31") (pin "2") (pinfunction "C2_2") (pintype "passive"))
      (node (ref "C34") (pin "2") (pinfunction "C2_2") (pintype "passive"))
      (node (ref "C59") (pin "1") (pinfunction "C1_1") (pintype "passive"))
      (node (ref "C7") (pin "1") (pinfunction "C1_1") (pintype "passive"))
      (node (ref "C80") (pin "2") (pinfunction "C2_2") (pintype "passive"))
      (node (ref "C81") (pin "1") (pinfunction "C1_1") (pintype "passive"))
      (node (ref "C82") (pin "2") (pinfunction "C2_2") (pintype "passive"))
      (node (ref "C86") (pin "2") (pinfunction "C2_2") (pintype "passive"))
      (node (ref "R16") (pin "1") (pinfunction "1_1") (pintype "passive"))
      (node (ref "R26") (pin "1") (pinfunction "1_1") (pintype "passive"))
      (node (ref "R30") (pin "1") (pinfunction "1_1") (pintype "passive"))
      (node (ref "R92") (pin "1") (pinfunction "1_1") (pintype "passive"))
      (node (ref "U1") (pin "2") (pinfunction "GND_2") (pintype "passive"))
      (node (ref "U18") (pin "16") (pinfunction "GND_16") (pintype "bidirectional"))
      (node (ref "U18") (pin "PAD") (pinfunction "GND_PAD_PAD") (pintype "bidirectional"))
      (node (ref "U4") (pin "14") (pinfunction "AC/~{DC}_14") (pintype "bidirectional"))
      (node (ref "U4") (pin "16") (pinfunction "GND_16") (pintype "bidirectional"))
      (node (ref "U4") (pin "PAD") (pinfunction "GND_PAD_PAD") (pintype "bidirectional"))
      (node (ref "U5") (pin "16") (pinfunction "AGND_16") (pintype "bidirectional"))
    )
    (net (code "24") (name "GPIO2_1") (class "Default")
      (node (ref "U5") (pin "2") (pinfunction "P2.1/SDA_2") (pintype "bidirectional"))
      (node (ref "X4") (pin "4") (pinfunction "S_4") (pintype "passive"))
    )
    (net (code "25") (name "HPDRIVE") (class "Default")
      (node (ref "C60") (pin "1") (pinfunction "C1_1") (pintype "passive"))
      (node (ref "U4") (pin "1") (pinfunction "HPDRIVE_1") (pintype "bidirectional"))
    )
    (net (code "26") (name "HPDRIVE2") (class "Default")
      (node (ref "C85") (pin "1") (pinfunction "C1_1") (pintype "passive"))
      (node (ref "U18") (pin "1") (pinfunction "HPDRIVE_1") (pintype "bidirectional"))
    )
    (net (code "27") (name "HPSENSE") (class "Default")
      (node (ref "C60") (pin "2") (pinfunction "C2_2") (pintype "passive"))
      (node (ref "R22") (pin "1") (pinfunction "1_1") (pintype "passive"))
      (node (ref "U4") (pin "20") (pinfunction "HPSENSE_20") (pintype "bidirectional"))
    )
    (net (code "28") (name "HPSENSE2") (class "Default")
      (node (ref "C85") (pin "2") (pinfunction "C2_2") (pintype "passive"))
      (node (ref "R77") (pin "1") (pinfunction "1_1") (pintype "passive"))
      (node (ref "U18") (pin "20") (pinfunction "HPSENSE_20") (pintype "bidirectional"))
    )
    (net (code "29") (name "IAOUT") (class "Default")
      (node (ref "C21") (pin "1") (pinfunction "C1_1") (pintype "passive"))
      (node (ref "R22") (pin "2") (pinfunction "2_2") (pintype "passive"))
      (node (ref "U4") (pin "19") (pinfunction "IAOUT_19") (pintype "bidirectional"))
    )
    (net (code "30") (name "IAOUT2") (class "Default")
      (node (ref "C83") (pin "1") (pinfunction "C1_1") (pintype "passive"))
      (node (ref "R77") (pin "2") (pinfunction "2_2") (pintype "passive"))
      (node (ref "U18") (pin "19") (pinfunction "IAOUT_19") (pintype "bidirectional"))
    )
    (net (code "31") (name "INA_OUT1") (class "Default")
      (node (ref "C14") (pin "1") (pinfunction "C1_1") (pintype "passive"))
      (node (ref "R14") (pin "2") (pinfunction "2_2") (pintype "passive"))
      (node (ref "TP14") (pin "TP") (pinfunction "TP_TP") (pintype "input"))
      (node (ref "U5") (pin "12") (pinfunction "AIN4_12") (pintype "bidirectional"))
    )
    (net (code "32") (name "INA_OUT2") (class "Default")
      (node (ref "C80") (pin "1") (pinfunction "C1_1") (pintype "passive"))
      (node (ref "R73") (pin "2") (pinfunction "2_2") (pintype "passive"))
      (node (ref "TP15") (pin "TP") (pinfunction "TP_TP") (pintype "input"))
      (node (ref "U5") (pin "27") (pinfunction "AIN10_27") (pintype "bidirectional"))
    )
    (net (code "36") (name "LED") (class "Default")
      (node (ref "R19") (pin "1") (pinfunction "1_1") (pintype "passive"))
      (node (ref "X6") (pin "10") (pinfunction "S_10") (pintype "passive"))
    )
    (net (code "37") (name "LOD1N") (class "Default")
      (node (ref "U4") (pin "11") (pinfunction "LO-_11") (pintype "bidirectional"))
      (node (ref "U5") (pin "11") (pinfunction "AIN3/VBIAS1_11") (pintype "bidirectional"))
    )
    (net (code "38") (name "LOD1P") (class "Default")
      (node (ref "U4") (pin "12") (pinfunction "LO+_12") (pintype "bidirectional"))
      (node (ref "U5") (pin "10") (pinfunction "AIN2_10") (pintype "bidirectional"))
    )
    (net (code "39") (name "LOD2N") (class "Default")
      (node (ref "TP5") (pin "TP") (pinfunction "TP_TP") (pintype "input"))
      (node (ref "U5") (pin "25") (pinfunction "AIN8_25") (pintype "bidirectional"))
    )
    (net (code "40") (name "LOD2P") (class "Default")
      (node (ref "U18") (pin "12") (pinfunction "LO+_12") (pintype "bidirectional"))
      (node (ref "U5") (pin "26") (pinfunction "AIN9/VBIAS4_26") (pintype "bidirectional"))
    )
    (net (code "41") (name "N$89") (class "Default")
      (node (ref "C190") (pin "2") (pinfunction "C2_2") (pintype "passive"))
      (node (ref "D1") (pin "2") (pinfunction "2_2") (pintype "passive"))
      (node (ref "L21") (pin "1") (pinfunction "1_1") (pintype "bidirectional"))
    )
    (net (code "42") (name "N$90") (class "Default")
      (node (ref "C191") (pin "2") (pinfunction "C2_2") (pintype "passive"))
      (node (ref "L22") (pin "1") (pinfunction "1_1") (pintype "bidirectional"))
      (node (ref "TR1") (pin "2") (pinfunction "2_2") (pintype "passive"))
      (node (ref "TR1A") (pin "1") (pinfunction "P1_1") (pintype "passive"))
    )
    (net (code "43") (name "NPLS") (class "Default")
      (node (ref "C69") (pin "1") (pinfunction "C1_1") (pintype "passive"))
      (node (ref "C70") (pin "1") (pinfunction "C1_1") (pintype "passive"))
      (node (ref "D6N") (pin "A") (pinfunction "A_A") (pintype "passive"))
      (node (ref "RL10") (pin "4") (pinfunction "DS1_4") (pintype "passive"))
      (node (ref "RL11") (pin "3") (pinfunction "DS2_3") (pintype "passive"))
      (node (ref "RL4") (pin "4") (pinfunction "DS1_4") (pintype "passive"))
      (node (ref "RL5") (pin "3") (pinfunction "DS2_3") (pintype "passive"))
    )
    (net (code "44") (name "Net-(C1-C2)") (class "Default")
      (node (ref "C1") (pin "2") (pinfunction "C2_2") (pintype "passive"))
      (node (ref "L8") (pin "2") (pinfunction "2_2") (pintype "bidirectional"))
      (node (ref "U1") (pin "1") (pinfunction "VIN_1") (pintype "power_in"))
      (node (ref "U1") (pin "3") (pinfunction "EN_3") (pintype "input"))
    )
    (net (code "45") (name "Net-(C4-C2)") (class "Default")
      (node (ref "C4") (pin "2") (pinfunction "C2_2") (pintype "passive"))
      (node (ref "C40") (pin "2") (pinfunction "C2_2") (pintype "passive"))
      (node (ref "L1") (pin "1") (pinfunction "1_1") (pintype "bidirectional"))
      (node (ref "L2") (pin "2") (pinfunction "2_2") (pintype "bidirectional"))
      (node (ref "R1") (pin "2") (pinfunction "2_2") (pintype "passive"))
      (node (ref "U3") (pin "6") (pinfunction "VBAT_6") (pintype "power_in"))
    )
    (net (code "46") (name "Net-(C7-C2)") (class "Default")
      (node (ref "C7") (pin "2") (pinfunction "C2_2") (pintype "passive"))
      (node (ref "L4") (pin "1") (pinfunction "1_1") (pintype "bidirectional"))
      (node (ref "U1") (pin "5") (pinfunction "VOUT_5") (pintype "output"))
    )
    (net (code "47") (name "Net-(C8-C2)") (class "Default")
      (node (ref "C8") (pin "2") (pinfunction "C2_2") (pintype "passive"))
      (node (ref "L6") (pin "2") (pinfunction "2_2") (pintype "bidirectional"))
      (node (ref "U2") (pin "1") (pinfunction "VIN_1") (pintype "power_in"))
      (node (ref "U2") (pin "3") (pinfunction "EN_3") (pintype "input"))
    )
    (net (code "48") (name "Net-(C9-C2)") (class "Default")
      (node (ref "C9") (pin "2") (pinfunction "C2_2") (pintype "passive"))
      (node (ref "L5") (pin "1") (pinfunction "1_1") (pintype "bidirectional"))
      (node (ref "U2") (pin "5") (pinfunction "VOUT_5") (pintype "output"))
    )
    (net (code "49") (name "Net-(C10-C1)") (class "Default")
      (node (ref "C10") (pin "1") (pinfunction "C1_1") (pintype "passive"))
      (node (ref "R12") (pin "2") (pinfunction "2_2") (pintype "passive"))
      (node (ref "R13") (pin "2") (pinfunction "2_2") (pintype "passive"))
      (node (ref "R18") (pin "1") (pinfunction "1_1") (pintype "passive"))
      (node (ref "U4") (pin "5") (pinfunction "RLD_5") (pintype "bidirectional"))
    )
    (net (code "50") (name "Net-(C10-C2)") (class "Default")
      (node (ref "C10") (pin "2") (pinfunction "C2_2") (pintype "passive"))
      (node (ref "U4") (pin "4") (pinfunction "RLDFB_4") (pintype "bidirectional"))
    )
    (net (code "51") (name "Net-(C10A-C1)") (class "Default")
      (node (ref "C10A") (pin "1") (pinfunction "C1_1") (pintype "passive"))
      (node (ref "R43") (pin "2") (pinfunction "2_2") (pintype "passive"))
      (node (ref "R46") (pin "2") (pinfunction "2_2") (pintype "passive"))
      (node (ref "U18") (pin "5") (pinfunction "RLD_5") (pintype "bidirectional"))
    )
    (net (code "52") (name "Net-(C10A-C2)") (class "Default")
      (node (ref "C10A") (pin "2") (pinfunction "C2_2") (pintype "passive"))
      (node (ref "U18") (pin "4") (pinfunction "RLDFB_4") (pintype "bidirectional"))
    )
    (net (code "53") (name "Net-(C11-C1)") (class "Default")
      (node (ref "C11") (pin "1") (pinfunction "C1_1") (pintype "passive"))
      (node (ref "R7") (pin "2") (pinfunction "2_2") (pintype "passive"))
      (node (ref "R8") (pin "1") (pinfunction "1_1") (pintype "passive"))
    )
    (net (code "54") (name "Net-(C17-C1)") (class "Default")
      (node (ref "C17") (pin "1") (pinfunction "C1_1") (pintype "passive"))
      (node (ref "R61") (pin "2") (pinfunction "2_2") (pintype "passive"))
      (node (ref "R67") (pin "1") (pinfunction "1_1") (pintype "passive"))
    )
    (net (code "55") (name "Net-(C22-C1)") (class "Default")
      (node (ref "C22") (pin "1") (pinfunction "C1_1") (pintype "passive"))
      (node (ref "IC17") (pin "3") (pinfunction "CFLY-_3") (pintype "bidirectional"))
    )
    (net (code "56") (name "Net-(C22-C2)") (class "Default")
      (node (ref "C22") (pin "2") (pinfunction "C2_2") (pintype "passive"))
      (node (ref "IC17") (pin "5") (pinfunction "CFLY+_5") (pintype "bidirectional"))
    )
    (net (code "57") (name "Net-(C23-C1)") (class "Default")
      (node (ref "C23") (pin "1") (pinfunction "C1_1") (pintype "passive"))
      (node (ref "C86") (pin "1") (pinfunction "C1_1") (pintype "passive"))
      (node (ref "R16") (pin "2") (pinfunction "2_2") (pintype "passive"))
      (node (ref "R17") (pin "1") (pinfunction "1_1") (pintype "passive"))
      (node (ref "U18") (pin "18") (pinfunction "REFIN_18") (pintype "bidirectional"))
      (node (ref "U4") (pin "18") (pinfunction "REFIN_18") (pintype "bidirectional"))
    )
    (net (code "58") (name "Net-(C26-C1)") (class "Default")
      (node (ref "C26") (pin "1") (pinfunction "C1_1") (pintype "passive"))
      (node (ref "C27") (pin "1") (pinfunction "C1_1") (pintype "passive"))
      (node (ref "U5") (pin "18") (pinfunction "AVDD_REG_18") (pintype "bidirectional"))
      (node (ref "U5") (pin "7") (pinfunction "REG_DVDD_7") (pintype "bidirectional"))
    )
    (net (code "59") (name "Net-(C32-C2)") (class "Default")
      (node (ref "C32") (pin "2") (pinfunction "C2_2") (pintype "passive"))
      (node (ref "U5") (pin "5") (pinfunction "XTALI_5") (pintype "bidirectional"))
      (node (ref "X1") (pin "2") (pinfunction "2_2") (pintype "passive"))
    )
    (net (code "60") (name "Net-(C33-C2)") (class "Default")
      (node (ref "C33") (pin "2") (pinfunction "C2_2") (pintype "passive"))
      (node (ref "U5") (pin "4") (pinfunction "XTALO_4") (pintype "bidirectional"))
      (node (ref "X1") (pin "1") (pinfunction "1_1") (pintype "passive"))
    )
    (net (code "61") (name "Net-(C34-C1)") (class "Default")
      (node (ref "C34") (pin "1") (pinfunction "C1_1") (pintype "passive"))
      (node (ref "U5") (pin "20") (pinfunction "INT_REF_20") (pintype "bidirectional"))
    )
    (net (code "62") (name "Net-(C44-C2)") (class "Default")
      (node (ref "C44") (pin "2") (pinfunction "C2_2") (pintype "passive"))
      (node (ref "D6P1") (pin "C") (pinfunction "C_C") (pintype "passive"))
      (node (ref "R48") (pin "2") (pinfunction "2_2") (pintype "passive"))
    )
    (net (code "63") (name "Net-(C45-C1)") (class "Default")
      (node (ref "C45") (pin "1") (pinfunction "C1_1") (pintype "passive"))
      (node (ref "R41") (pin "1") (pinfunction "1_1") (pintype "passive"))
      (node (ref "R42") (pin "2") (pinfunction "2_2") (pintype "passive"))
    )
    (net (code "64") (name "Net-(C45-C2)") (class "Default")
      (node (ref "C45") (pin "2") (pinfunction "C2_2") (pintype "passive"))
      (node (ref "D8") (pin "1") (pinfunction "A1_1") (pintype "passive"))
      (node (ref "R42") (pin "1") (pinfunction "1_1") (pintype "passive"))
      (node (ref "T25") (pin "1") (pinfunction "G_1") (pintype "passive"))
    )
    (net (code "65") (name "Net-(C50-C1)") (class "Default")
      (node (ref "C50") (pin "1") (pinfunction "C1_1") (pintype "passive"))
      (node (ref "D6P2") (pin "A") (pinfunction "A_A") (pintype "passive"))
      (node (ref "R49") (pin "2") (pinfunction "2_2") (pintype "passive"))
    )
    (net (code "66") (name "Net-(C53-C2)") (class "Default")
      (node (ref "C53") (pin "2") (pinfunction "C2_2") (pintype "passive"))
      (node (ref "C54") (pin "1") (pinfunction "C1_1") (pintype "passive"))
      (node (ref "X7") (pin "13") (pinfunction "S_13") (pintype "passive"))
    )
    (net (code "67") (name "Net-(C67-C1)") (class "Default")
      (node (ref "C67") (pin "1") (pinfunction "C1_1") (pintype "passive"))
      (node (ref "R29") (pin "1") (pinfunction "1_1") (pintype "passive"))
      (node (ref "R40") (pin "2") (pinfunction "2_2") (pintype "passive"))
    )
    (net (code "68") (name "Net-(C67-C2)") (class "Default")
      (node (ref "C67") (pin "2") (pinfunction "C2_2") (pintype "passive"))
      (node (ref "D22") (pin "3") (pinfunction "C1A2_3") (pintype "passive"))
      (node (ref "R40") (pin "1") (pinfunction "1_1") (pintype "passive"))
      (node (ref "T4") (pin "1") (pinfunction "G_1") (pintype "passive"))
      (node (ref "U17") (pin "5") (pinfunction "IN+_5") (pintype "input"))
    )
    (net (code "69") (name "Net-(C75-C1)") (class "Default")
      (node (ref "C75") (pin "1") (pinfunction "C1_1") (pintype "passive"))
      (node (ref "R57") (pin "2") (pinfunction "2_2") (pintype "passive"))
      (node (ref "R63") (pin "2") (pinfunction "2_2") (pintype "passive"))
      (node (ref "U15") (pin "6") (pinfunction "IN-_6") (pintype "input"))
    )
    (net (code "70") (name "Net-(C75-C2)") (class "Default")
      (node (ref "C75") (pin "2") (pinfunction "C2_2") (pintype "passive"))
      (node (ref "R29") (pin "2") (pinfunction "2_2") (pintype "passive"))
      (node (ref "R57") (pin "1") (pinfunction "1_1") (pintype "passive"))
      (node (ref "U15") (pin "7") (pinfunction "OUT_7") (pintype "output"))
    )
    (net (code "71") (name "Net-(C76-C1)") (class "Default")
      (node (ref "C76") (pin "1") (pinfunction "C1_1") (pintype "passive"))
      (node (ref "R55") (pin "2") (pinfunction "2_2") (pintype "passive"))
      (node (ref "R56") (pin "2") (pinfunction "2_2") (pintype "passive"))
      (node (ref "U16") (pin "6") (pinfunction "IN-_6") (pintype "input"))
    )
    (net (code "72") (name "Net-(C76-C2)") (class "Default")
      (node (ref "C76") (pin "2") (pinfunction "C2_2") (pintype "passive"))
      (node (ref "R41") (pin "2") (pinfunction "2_2") (pintype "passive"))
      (node (ref "R56") (pin "1") (pinfunction "1_1") (pintype "passive"))
      (node (ref "TP20") (pin "TP") (pinfunction "TP_TP") (pintype "input"))
      (node (ref "U16") (pin "7") (pinfunction "OUT_7") (pintype "output"))
    )
    (net (code "73") (name "Net-(C144-C2)") (class "Default")
      (node (ref "C144") (pin "2") (pinfunction "C2_2") (pintype "passive"))
      (node (ref "R144") (pin "1") (pinfunction "1_1") (pintype "passive"))
      (node (ref "R145") (pin "2") (pinfunction "2_2") (pintype "passive"))
      (node (ref "U16") (pin "5") (pinfunction "IN+_5") (pintype "input"))
    )
    (net (code "74") (name "Net-(D2-A1)") (class "Default")
      (node (ref "D2") (pin "1") (pinfunction "A1_1") (pintype "passive"))
      (node (ref "R80") (pin "1") (pinfunction "1_1") (pintype "passive"))
    )
    (net (code "75") (name "Net-(D6P1-PadA)") (class "Default")
      (node (ref "D6P1") (pin "A") (pinfunction "A_A") (pintype "passive"))
      (node (ref "L11") (pin "1") (pinfunction "1_1") (pintype "bidirectional"))
    )
    (net (code "76") (name "Net-(D6P2-PadC)") (class "Default")
      (node (ref "D6P2") (pin "C") (pinfunction "C_C") (pintype "passive"))
      (node (ref "L12") (pin "2") (pinfunction "2_2") (pintype "bidirectional"))
    )
    (net (code "77") (name "Net-(D12-C1A2)") (class "Default")
      (node (ref "D12") (pin "3") (pinfunction "C1A2_3") (pintype "passive"))
      (node (ref "RSENSE") (pin "1") (pinfunction "1_1") (pintype "passive"))
      (node (ref "T25") (pin "3") (pinfunction "S_3") (pintype "passive"))
      (node (ref "U16") (pin "3") (pinfunction "IN+_3") (pintype "input"))
    )
    (net (code "78") (name "Net-(D21-2C)") (class "Default")
      (node (ref "D21") (pin "K") (pinfunction "2C_K") (pintype "passive"))
      (node (ref "TR1") (pin "4") (pinfunction "4_4") (pintype "passive"))
      (node (ref "TR1A") (pin "7") (pinfunction "P7_7") (pintype "passive"))
      (node (ref "TR1A") (pin "8") (pinfunction "P8_8") (pintype "passive"))
      (node (ref "U13") (pin "4") (pinfunction "SW_4") (pintype "bidirectional"))
      (node (ref "U13") (pin "5") (pinfunction "SW_5") (pintype "bidirectional"))
    )
    (net (code "79") (name "Net-(F1-Pad2)") (class "Default")
      (node (ref "F1") (pin "2") (pinfunction "2_2") (pintype "passive"))
      (node (ref "PMOS1") (pin "D0") (pinfunction "D0_D0") (pintype "bidirectional"))
      (node (ref "PMOS1") (pin "D1") (pinfunction "D1_D1") (pintype "bidirectional"))
      (node (ref "PMOS1") (pin "D2") (pinfunction "D2_D2") (pintype "bidirectional"))
      (node (ref "PMOS1") (pin "D3") (pinfunction "D3_D3") (pintype "bidirectional"))
      (node (ref "PMOS1") (pin "D4") (pinfunction "D4_D4") (pintype "bidirectional"))
    )
    (net (code "80") (name "Net-(IC1-+IN)") (class "Default")
      (node (ref "IC1") (pin "3") (pinfunction "+IN_3") (pintype "input"))
      (node (ref "U5") (pin "19") (pinfunction "DAC_19") (pintype "bidirectional"))
    )
    (net (code "81") (name "Net-(RL3-K)") (class "Default")
      (node (ref "RL3") (pin "2") (pinfunction "K_2") (pintype "passive"))
      (node (ref "RL4") (pin "1") (pinfunction "A_1") (pintype "passive"))
    )
    (net (code "82") (name "Net-(RL5-K)") (class "Default")
      (node (ref "RL5") (pin "2") (pinfunction "K_2") (pintype "passive"))
      (node (ref "RL6") (pin "1") (pinfunction "A_1") (pintype "passive"))
    )
    (net (code "83") (name "Net-(RL7-DS1)") (class "Default")
      (node (ref "R48") (pin "1") (pinfunction "1_1") (pintype "passive"))
      (node (ref "RL7") (pin "4") (pinfunction "DS1_4") (pintype "passive"))
    )
    (net (code "84") (name "Net-(RL7-K)") (class "Default")
      (node (ref "RL7") (pin "2") (pinfunction "K_2") (pintype "passive"))
      (node (ref "RL8") (pin "1") (pinfunction "A_1") (pintype "passive"))
    )
    (net (code "85") (name "Net-(RL8-DS1)") (class "Default")
      (node (ref "R49") (pin "1") (pinfunction "1_1") (pintype "passive"))
      (node (ref "RL8") (pin "4") (pinfunction "DS1_4") (pintype "passive"))
    )
    (net (code "86") (name "Net-(RL10-A)") (class "Default")
      (node (ref "RL10") (pin "1") (pinfunction "A_1") (pintype "passive"))
      (node (ref "RL9") (pin "2") (pinfunction "K_2") (pintype "passive"))
    )
    (net (code "87") (name "Net-(RL11-K)") (class "Default")
      (node (ref "RL11") (pin "2") (pinfunction "K_2") (pintype "passive"))
      (node (ref "RL12") (pin "1") (pinfunction "A_1") (pintype "passive"))
    )
    (net (code "88") (name "Net-(T4-S)") (class "Default")
      (node (ref "RSENSE") (pin "2") (pinfunction "2_2") (pintype "passive"))
      (node (ref "T4") (pin "3") (pinfunction "S_3") (pintype "passive"))
      (node (ref "U15") (pin "3") (pinfunction "IN+_3") (pintype "input"))
    )
    (net (code "89") (name "Net-(TR1A-P4)") (class "Default")
      (node (ref "D1") (pin "1") (pinfunction "1_1") (pintype "input"))
      (node (ref "TR1") (pin "3") (pinfunction "3_3") (pintype "passive"))
      (node (ref "TR1A") (pin "4") (pinfunction "P4_4") (pintype "passive"))
    )
    (net (code "90") (name "Net-(U3-FB)") (class "Default")
      (node (ref "R3") (pin "2") (pinfunction "2_2") (pintype "passive"))
      (node (ref "R4") (pin "1") (pinfunction "1_1") (pintype "passive"))
      (node (ref "U3") (pin "3") (pinfunction "FB_3") (pintype "input"))
    )
    (net (code "91") (name "Net-(U3-SW)") (class "Default")
      (node (ref "L1") (pin "2") (pinfunction "2_2") (pintype "bidirectional"))
      (node (ref "U3") (pin "9") (pinfunction "SW_9") (pintype "input"))
    )
    (net (code "92") (name "Net-(U4-+IN)") (class "Default")
      (node (ref "R5") (pin "2") (pinfunction "2_2") (pintype "passive"))
      (node (ref "U4") (pin "2") (pinfunction "+IN_2") (pintype "bidirectional"))
    )
    (net (code "93") (name "Net-(U4--IN)") (class "Default")
      (node (ref "R6") (pin "2") (pinfunction "2_2") (pintype "passive"))
      (node (ref "U4") (pin "3") (pinfunction "-IN_3") (pintype "bidirectional"))
    )
    (net (code "94") (name "Net-(U5-AIN5{slash}VBIAS2{slash}IEXC)") (class "Default")
      (node (ref "TP4") (pin "TP") (pinfunction "TP_TP") (pintype "input"))
      (node (ref "U5") (pin "22") (pinfunction "AIN5/VBIAS2/IEXC_22") (pintype "bidirectional"))
    )
    (net (code "95") (name "Net-(U5-AIN6{slash}IEXC)") (class "Default")
      (node (ref "TP1") (pin "TP") (pinfunction "TP_TP") (pintype "input"))
      (node (ref "U5") (pin "23") (pinfunction "AIN6/IEXC_23") (pintype "bidirectional"))
    )
    (net (code "96") (name "Net-(U5-AIN7{slash}VBIAS3{slash}IEXC)") (class "Default")
      (node (ref "TP3") (pin "TP") (pinfunction "TP_TP") (pintype "input"))
      (node (ref "U5") (pin "24") (pinfunction "AIN7/VBIAS3/IEXC_24") (pintype "bidirectional"))
    )
    (net (code "97") (name "Net-(U5-GND_SW)") (class "Default")
      (node (ref "TP2") (pin "TP") (pinfunction "TP_TP") (pintype "input"))
      (node (ref "U5") (pin "13") (pinfunction "GND_SW_13") (pintype "bidirectional"))
    )
    (net (code "98") (name "Net-(U5-IREF)") (class "Default")
      (node (ref "R26") (pin "2") (pinfunction "2_2") (pintype "passive"))
      (node (ref "U5") (pin "21") (pinfunction "IREF_21") (pintype "bidirectional"))
    )
    (net (code "99") (name "Net-(U5-P0.0{slash}MISO1)") (class "Default")
      (node (ref "R21") (pin "2") (pinfunction "2_2") (pintype "passive"))
      (node (ref "U5") (pin "29") (pinfunction "P0.0/MISO1_29") (pintype "bidirectional"))
    )
    (net (code "100") (name "Net-(U5-P0.4{slash}RTS{slash}ECLK0)") (class "Default")
      (node (ref "R19") (pin "2") (pinfunction "2_2") (pintype "passive"))
      (node (ref "U5") (pin "33") (pinfunction "P0.4/RTS/ECLK0_33") (pintype "bidirectional"))
    )
    (net (code "101") (name "Net-(U13-CHARGE)") (class "Default")
      (node (ref "L3") (pin "1") (pinfunction "1_1") (pintype "bidirectional"))
      (node (ref "R28") (pin "2") (pinfunction "2_2") (pintype "passive"))
      (node (ref "U13") (pin "2") (pinfunction "CHARGE_2") (pintype "bidirectional"))
    )
    (net (code "102") (name "Net-(U15B-IN+)") (class "Default")
      (node (ref "R64") (pin "2") (pinfunction "2_2") (pintype "passive"))
      (node (ref "R65") (pin "2") (pinfunction "2_2") (pintype "passive"))
      (node (ref "TP17") (pin "TP") (pinfunction "TP_TP") (pintype "input"))
      (node (ref "U15") (pin "5") (pinfunction "IN+_5") (pintype "input"))
    )
    (net (code "103") (name "Net-(U16A-IN-)") (class "Default")
      (node (ref "R55") (pin "1") (pinfunction "1_1") (pintype "passive"))
      (node (ref "U16") (pin "1") (pinfunction "OUT_1") (pintype "output"))
      (node (ref "U16") (pin "2") (pinfunction "IN-_2") (pintype "input"))
    )
    (net (code "104") (name "Net-(U17A-IN-)") (class "Default")
      (node (ref "R68") (pin "1") (pinfunction "1_1") (pintype "passive"))
      (node (ref "R69") (pin "2") (pinfunction "2_2") (pintype "passive"))
      (node (ref "U17") (pin "2") (pinfunction "IN-_2") (pintype "input"))
    )
    (net (code "105") (name "Net-(U17A-OUT)") (class "Default")
      (node (ref "R64") (pin "1") (pinfunction "1_1") (pintype "passive"))
      (node (ref "R69") (pin "1") (pinfunction "1_1") (pintype "passive"))
      (node (ref "U17") (pin "1") (pinfunction "OUT_1") (pintype "output"))
    )
    (net (code "106") (name "Net-(U17B-IN-)") (class "Default")
      (node (ref "R80") (pin "2") (pinfunction "2_2") (pintype "passive"))
      (node (ref "U17") (pin "6") (pinfunction "IN-_6") (pintype "input"))
      (node (ref "U17") (pin "7") (pinfunction "OUT_7") (pintype "output"))
    )
    (net (code "107") (name "Net-(U18-+IN)") (class "Default")
      (node (ref "R15") (pin "2") (pinfunction "2_2") (pintype "passive"))
      (node (ref "U18") (pin "2") (pinfunction "+IN_2") (pintype "bidirectional"))
    )
    (net (code "108") (name "Net-(U18--IN)") (class "Default")
      (node (ref "R20") (pin "2") (pinfunction "2_2") (pintype "passive"))
      (node (ref "U18") (pin "3") (pinfunction "-IN_3") (pintype "bidirectional"))
    )
    (net (code "109") (name "Net-(X7Q-S)") (class "Default")
      (node (ref "X7") (pin "6") (pinfunction "S_6") (pintype "passive"))
      (node (ref "X7") (pin "7") (pinfunction "S_7") (pintype "passive"))
    )
    (net (code "110") (name "Net-(ZD1-A)") (class "Default")
      (node (ref "R25") (pin "1") (pinfunction "1_1") (pintype "passive"))
      (node (ref "ZD1") (pin "2A") (pinfunction "A_2A") (pintype "passive"))
    )
    (net (code "111") (name "Net-(ZD3-C)") (class "Default")
      (node (ref "R23") (pin "1") (pinfunction "1_1") (pintype "passive"))
      (node (ref "ZD3") (pin "1C") (pinfunction "C_1C") (pintype "passive"))
    )
    (net (code "112") (name "OA+") (class "Default")
      (node (ref "C12") (pin "2") (pinfunction "C2_2") (pintype "passive"))
      (node (ref "R8") (pin "2") (pinfunction "2_2") (pintype "passive"))
      (node (ref "U4") (pin "7") (pinfunction "OPAMP+_7") (pintype "bidirectional"))
    )
    (net (code "113") (name "OA+2") (class "Default")
      (node (ref "C18") (pin "2") (pinfunction "C2_2") (pintype "passive"))
      (node (ref "R67") (pin "2") (pinfunction "2_2") (pintype "passive"))
      (node (ref "U18") (pin "7") (pinfunction "OPAMP+_7") (pintype "bidirectional"))
    )
    (net (code "114") (name "OA-") (class "Default")
      (node (ref "R10") (pin "2") (pinfunction "2_2") (pintype "passive"))
      (node (ref "R11") (pin "1") (pinfunction "1_1") (pintype "passive"))
      (node (ref "U4") (pin "9") (pinfunction "OPAMP-_9") (pintype "bidirectional"))
    )
    (net (code "115") (name "OA-2") (class "Default")
      (node (ref "R71") (pin "2") (pinfunction "2_2") (pintype "passive"))
      (node (ref "R72") (pin "1") (pinfunction "1_1") (pintype "passive"))
      (node (ref "U18") (pin "9") (pinfunction "OPAMP-_9") (pintype "bidirectional"))
    )
    (net (code "116") (name "OUT") (class "Default")
      (node (ref "C11") (pin "2") (pinfunction "C2_2") (pintype "passive"))
      (node (ref "R10") (pin "1") (pinfunction "1_1") (pintype "passive"))
      (node (ref "R14") (pin "1") (pinfunction "1_1") (pintype "passive"))
      (node (ref "U4") (pin "10") (pinfunction "OUT_10") (pintype "bidirectional"))
    )
    (net (code "117") (name "OUT2") (class "Default")
      (node (ref "C17") (pin "2") (pinfunction "C2_2") (pintype "passive"))
      (node (ref "R71") (pin "1") (pinfunction "1_1") (pintype "passive"))
      (node (ref "R73") (pin "1") (pinfunction "1_1") (pintype "passive"))
      (node (ref "U18") (pin "10") (pinfunction "OUT_10") (pintype "bidirectional"))
    )
    (net (code "118") (name "PPLS") (class "Default")
      (node (ref "C46") (pin "2") (pinfunction "C2_2") (pintype "passive"))
      (node (ref "C51") (pin "2") (pinfunction "C2_2") (pintype "passive"))
      (node (ref "D6P") (pin "C") (pinfunction "C_C") (pintype "passive"))
      (node (ref "RL12") (pin "3") (pinfunction "DS2_3") (pintype "passive"))
      (node (ref "RL3") (pin "3") (pinfunction "DS2_3") (pintype "passive"))
      (node (ref "RL6") (pin "3") (pinfunction "DS2_3") (pintype "passive"))
      (node (ref "RL9") (pin "3") (pinfunction "DS2_3") (pintype "passive"))
    )
    (net (code "119") (name "PS_ENA") (class "Default")
      (node (ref "C40") (pin "1") (pinfunction "C1_1") (pintype "passive"))
      (node (ref "R21") (pin "1") (pinfunction "1_1") (pintype "passive"))
      (node (ref "U3") (pin "1") (pinfunction "EN_1") (pintype "input"))
    )
    (net (code "120") (name "REFOUT") (class "Default")
      (node (ref "C12") (pin "1") (pinfunction "C1_1") (pintype "passive"))
      (node (ref "R11") (pin "2") (pinfunction "2_2") (pintype "passive"))
      (node (ref "R9") (pin "2") (pinfunction "2_2") (pintype "passive"))
      (node (ref "U4") (pin "8") (pinfunction "REFOUT_8") (pintype "bidirectional"))
    )
    (net (code "121") (name "REFOUT2") (class "Default")
      (node (ref "C18") (pin "1") (pinfunction "C1_1") (pintype "passive"))
      (node (ref "R70") (pin "2") (pinfunction "2_2") (pintype "passive"))
      (node (ref "R72") (pin "2") (pinfunction "2_2") (pintype "passive"))
      (node (ref "U18") (pin "8") (pinfunction "REFOUT_8") (pintype "bidirectional"))
    )
    (net (code "122") (name "RESET") (class "Default")
      (node (ref "R89") (pin "2") (pinfunction "2_2") (pintype "passive"))
      (node (ref "U5") (pin "1") (pinfunction "RESET_1") (pintype "bidirectional"))
      (node (ref "X4") (pin "5") (pinfunction "S_5") (pintype "passive"))
    )
    (net (code "123") (name "SA1") (class "Default")
      (node (ref "RL4") (pin "3") (pinfunction "DS2_3") (pintype "passive"))
      (node (ref "RL6") (pin "4") (pinfunction "DS1_4") (pintype "passive"))
      (node (ref "X7") (pin "17") (pinfunction "S_17") (pintype "passive"))
    )
    (net (code "124") (name "SA2") (class "Default")
      (node (ref "RL3") (pin "4") (pinfunction "DS1_4") (pintype "passive"))
      (node (ref "RL5") (pin "4") (pinfunction "DS1_4") (pintype "passive"))
      (node (ref "X7") (pin "18") (pinfunction "S_18") (pintype "passive"))
    )
    (net (code "125") (name "SAINV") (class "Default")
      (node (ref "R83") (pin "1") (pinfunction "1_1") (pintype "passive"))
      (node (ref "U5") (pin "40") (pinfunction "P1.2/PWM0_40") (pintype "bidirectional"))
    )
    (net (code "126") (name "SAPOS") (class "Default")
      (node (ref "R84") (pin "1") (pinfunction "1_1") (pintype "passive"))
      (node (ref "U5") (pin "41") (pinfunction "P1.3/PWM1_41") (pintype "bidirectional"))
    )
    (net (code "127") (name "SB1") (class "Default")
      (node (ref "RL11") (pin "4") (pinfunction "DS1_4") (pintype "passive"))
      (node (ref "RL9") (pin "4") (pinfunction "DS1_4") (pintype "passive"))
      (node (ref "X7") (pin "19") (pinfunction "S_19") (pintype "passive"))
    )
    (net (code "128") (name "SB2") (class "Default")
      (node (ref "RL10") (pin "3") (pinfunction "DS2_3") (pintype "passive"))
      (node (ref "RL12") (pin "4") (pinfunction "DS1_4") (pintype "passive"))
      (node (ref "X7") (pin "20") (pinfunction "S_20") (pintype "passive"))
    )
    (net (code "129") (name "SBINV") (class "Default")
      (node (ref "R51") (pin "1") (pinfunction "1_1") (pintype "passive"))
      (node (ref "U5") (pin "38") (pinfunction "P1.0/IRQ3/PWMSYNC/ECLKI_38") (pintype "bidirectional"))
    )
    (net (code "130") (name "SBPOS") (class "Default")
      (node (ref "R58") (pin "1") (pinfunction "1_1") (pintype "passive"))
      (node (ref "U5") (pin "39") (pinfunction "P1.1/IRQ4/PWMTRIP_39") (pintype "bidirectional"))
    )
    (net (code "131") (name "SPI_CE") (class "Default")
      (node (ref "CE") (pin "TP") (pinfunction "TP_TP") (pintype "input"))
      (node (ref "U5") (pin "45") (pinfunction "P1.7/IRQ7/PWM5/SS0_45") (pintype "bidirectional"))
    )
    (net (code "132") (name "SPI_CK") (class "Default")
      (node (ref "CK") (pin "TP") (pinfunction "TP_TP") (pintype "input"))
      (node (ref "U5") (pin "43") (pinfunction "P1.5/IRQ5/PWM3/SCLK0_43") (pintype "bidirectional"))
    )
    (net (code "133") (name "SPI_MISO") (class "Default")
      (node (ref "SO") (pin "TP") (pinfunction "TP_TP") (pintype "input"))
      (node (ref "U5") (pin "42") (pinfunction "P1.4/PWM2/MISO0_42") (pintype "bidirectional"))
    )
    (net (code "134") (name "SPI_MOSI") (class "Default")
      (node (ref "SI") (pin "TP") (pinfunction "TP_TP") (pintype "input"))
      (node (ref "U5") (pin "44") (pinfunction "P1.6/IRQ6/PWM4/MOSI0_44") (pintype "bidirectional"))
    )
    (net (code "135") (name "SW") (class "Default")
      (node (ref "C21") (pin "2") (pinfunction "C2_2") (pintype "passive"))
      (node (ref "R7") (pin "1") (pinfunction "1_1") (pintype "passive"))
      (node (ref "R9") (pin "1") (pinfunction "1_1") (pintype "passive"))
      (node (ref "U4") (pin "6") (pinfunction "SW_6") (pintype "bidirectional"))
    )
    (net (code "136") (name "SW2") (class "Default")
      (node (ref "C83") (pin "2") (pinfunction "C2_2") (pintype "passive"))
      (node (ref "R61") (pin "1") (pinfunction "1_1") (pintype "passive"))
      (node (ref "R70") (pin "1") (pinfunction "1_1") (pintype "passive"))
      (node (ref "U18") (pin "6") (pinfunction "SW_6") (pintype "bidirectional"))
    )
    (net (code "137") (name "SWCLK") (class "Default")
      (node (ref "U5") (pin "47") (pinfunction "SWCLK_47") (pintype "bidirectional"))
      (node (ref "X4") (pin "7") (pinfunction "S_7") (pintype "passive"))
    )
    (net (code "138") (name "SWDIO") (class "Default")
      (node (ref "R24") (pin "1") (pinfunction "1_1") (pintype "passive"))
      (node (ref "U5") (pin "48") (pinfunction "SWDIO_48") (pintype "bidirectional"))
      (node (ref "X4") (pin "6") (pinfunction "S_6") (pintype "passive"))
    )
    (net (code "139") (name "SW_CTRL") (class "Default")
      (node (ref "R91") (pin "1") (pinfunction "1_1") (pintype "passive"))
      (node (ref "U5") (pin "34") (pinfunction "P0.5/CTS_34") (pintype "bidirectional"))
    )
    (net (code "140") (name "UART_RX") (class "Default")
      (node (ref "U5") (pin "30") (pinfunction "P0.1/SCLK1/SCL/SIN_30") (pintype "bidirectional"))
      (node (ref "X4") (pin "3") (pinfunction "S_3") (pintype "passive"))
      (node (ref "X6") (pin "15") (pinfunction "S_15") (pintype "passive"))
    )
    (net (code "141") (name "UART_TX") (class "Default")
      (node (ref "U5") (pin "31") (pinfunction "P0.2/MOSI/SDA/SOUT_31") (pintype "bidirectional"))
      (node (ref "X4") (pin "2") (pinfunction "S_2") (pintype "passive"))
      (node (ref "X6") (pin "14") (pinfunction "S_14") (pintype "passive"))
    )
    (net (code "142") (name "VA+") (class "Default")
      (node (ref "C1U15") (pin "2") (pinfunction "C2_2") (pintype "passive"))
      (node (ref "C2U16") (pin "2") (pinfunction "C2_2") (pintype "passive"))
      (node (ref "C38") (pin "2") (pinfunction "C2_2") (pintype "passive"))
      (node (ref "C42") (pin "1") (pinfunction "C1_1") (pintype "passive"))
      (node (ref "C47") (pin "1") (pinfunction "1_1") (pintype "passive"))
      (node (ref "CU17") (pin "2") (pinfunction "C2_2") (pintype "passive"))
      (node (ref "D12") (pin "2") (pinfunction "C2_2") (pintype "passive"))
      (node (ref "IC17") (pin "2") (pinfunction "VIN_2") (pintype "power_in"))
      (node (ref "L9") (pin "2") (pinfunction "2_2") (pintype "bidirectional"))
      (node (ref "R145") (pin "1") (pinfunction "1_1") (pintype "passive"))
      (node (ref "R68") (pin "2") (pinfunction "2_2") (pintype "passive"))
      (node (ref "U15") (pin "8") (pinfunction "V+_8") (pintype "power_in"))
      (node (ref "U16") (pin "8") (pinfunction "V+_8") (pintype "power_in"))
      (node (ref "U17") (pin "8") (pinfunction "V+_8") (pintype "power_in"))
      (node (ref "X9") (pin "12") (pinfunction "S_12") (pintype "passive"))
    )
    (net (code "143") (name "VA-") (class "Default")
      (node (ref "C1U16") (pin "1") (pinfunction "C1_1") (pintype "passive"))
      (node (ref "C2U15") (pin "1") (pinfunction "C1_1") (pintype "passive"))
      (node (ref "C58") (pin "2") (pinfunction "C2_2") (pintype "passive"))
      (node (ref "C88") (pin "1") (pinfunction "C1_1") (pintype "passive"))
      (node (ref "D12") (pin "1") (pinfunction "A1_1") (pintype "passive"))
      (node (ref "L10") (pin "2") (pinfunction "2_2") (pintype "bidirectional"))
      (node (ref "R144") (pin "2") (pinfunction "2_2") (pintype "passive"))
      (node (ref "R65") (pin "1") (pinfunction "1_1") (pintype "passive"))
      (node (ref "U15") (pin "4") (pinfunction "V-_4") (pintype "power_in"))
      (node (ref "U16") (pin "4") (pinfunction "V-_4") (pintype "power_in"))
      (node (ref "X9") (pin "13") (pinfunction "S_13") (pintype "passive"))
    )
    (net (code "144") (name "VBATTEXT") (class "Default")
      (node (ref "C55") (pin "2") (pinfunction "2_2") (pintype "passive"))
      (node (ref "F1") (pin "1") (pinfunction "1_1") (pintype "passive"))
      (node (ref "X6") (pin "6") (pinfunction "S_6") (pintype "passive"))
      (node (ref "X6") (pin "7") (pinfunction "S_7") (pintype "passive"))
    )
    (net (code "145") (name "VBATTSENSE") (class "Default")
      (node (ref "R1") (pin "1") (pinfunction "1_1") (pintype "passive"))
      (node (ref "R2") (pin "2") (pinfunction "2_2") (pintype "passive"))
      (node (ref "U5") (pin "28") (pinfunction "AIN11/VBIAS5_28") (pintype "bidirectional"))
    )
    (net (code "146") (name "VBATT_INT") (class "Default")
      (node (ref "C2") (pin "2") (pinfunction "C2_2") (pintype "passive"))
      (node (ref "C3") (pin "2") (pinfunction "C2_2") (pintype "passive"))
      (node (ref "C39") (pin "2") (pinfunction "C2_2") (pintype "passive"))
      (node (ref "L2") (pin "1") (pinfunction "1_1") (pintype "bidirectional"))
      (node (ref "PMOS1") (pin "S1") (pinfunction "S1_S1") (pintype "bidirectional"))
      (node (ref "PMOS1") (pin "S2") (pinfunction "S2_S2") (pintype "bidirectional"))
      (node (ref "PMOS1") (pin "S3") (pinfunction "S3_S3") (pintype "bidirectional"))
      (node (ref "TR1") (pin "1") (pinfunction "1_1") (pintype "passive"))
      (node (ref "TR1A") (pin "5") (pinfunction "P5_5") (pintype "passive"))
      (node (ref "TR1A") (pin "6") (pinfunction "P6_6") (pintype "passive"))
      (node (ref "U13") (pin "6") (pinfunction "VBATT_6") (pintype "bidirectional"))
    )
    (net (code "147") (name "VCCSSENS") (class "Default")
      (node (ref "R63") (pin "1") (pinfunction "1_1") (pintype "passive"))
      (node (ref "TP16") (pin "TP") (pinfunction "TP_TP") (pintype "input"))
      (node (ref "U15") (pin "1") (pinfunction "OUT_1") (pintype "output"))
      (node (ref "U15") (pin "2") (pinfunction "IN-_2") (pintype "input"))
    )
    (net (code "148") (name "VCCS_CHRG_DRIVE") (class "Default")
      (node (ref "R66") (pin "1") (pinfunction "1_1") (pintype "passive"))
      (node (ref "RL7") (pin "1") (pinfunction "A_1") (pintype "passive"))
      (node (ref "X9") (pin "3") (pinfunction "S_3") (pintype "passive"))
    )
    (net (code "149") (name "VCCS_PEAK_SENS") (class "Default")
      (node (ref "C49") (pin "1") (pinfunction "C1_1") (pintype "passive"))
      (node (ref "D2") (pin "2") (pinfunction "C2_2") (pintype "passive"))
      (node (ref "D2") (pin "3") (pinfunction "C1A2_3") (pintype "passive"))
      (node (ref "R62") (pin "2") (pinfunction "2_2") (pintype "passive"))
      (node (ref "U5") (pin "8") (pinfunction "AIN0_8") (pintype "bidirectional"))
      (node (ref "X9") (pin "4") (pinfunction "S_4") (pintype "passive"))
    )
    (net (code "150") (name "VCC_3V6") (class "Default")
      (node (ref "C5") (pin "2") (pinfunction "C2_2") (pintype "passive"))
      (node (ref "C6") (pin "2") (pinfunction "C2_2") (pintype "passive"))
      (node (ref "L6") (pin "1") (pinfunction "1_1") (pintype "bidirectional"))
      (node (ref "L8") (pin "1") (pinfunction "1_1") (pintype "bidirectional"))
      (node (ref "L9") (pin "1") (pinfunction "1_1") (pintype "bidirectional"))
      (node (ref "R4") (pin "2") (pinfunction "2_2") (pintype "passive"))
      (node (ref "U3") (pin "2") (pinfunction "VOUT_2") (pintype "output"))
    )
    (net (code "151") (name "VIOUT") (class "Default")
      (node (ref "IC1") (pin "1") (pinfunction "OUT_1") (pintype "output"))
      (node (ref "IC1") (pin "4") (pinfunction "-IN_4") (pintype "input"))
      (node (ref "U17") (pin "3") (pinfunction "IN+_3") (pintype "input"))
      (node (ref "X9") (pin "2") (pinfunction "S_2") (pintype "passive"))
    )
    (net (code "152") (name "VNN") (class "Default")
      (node (ref "C15") (pin "2") (pinfunction "C2_2") (pintype "passive"))
      (node (ref "L12") (pin "1") (pinfunction "1_1") (pintype "bidirectional"))
      (node (ref "L22") (pin "2") (pinfunction "2_2") (pintype "bidirectional"))
      (node (ref "R25") (pin "2") (pinfunction "2_2") (pintype "passive"))
      (node (ref "X9") (pin "10") (pinfunction "S_10") (pintype "passive"))
    )
    (net (code "153") (name "VNNCHG") (class "Default")
      (node (ref "C46") (pin "1") (pinfunction "C1_1") (pintype "passive"))
      (node (ref "C51") (pin "1") (pinfunction "C1_1") (pintype "passive"))
      (node (ref "RL8") (pin "3") (pinfunction "DS2_3") (pintype "passive"))
      (node (ref "T25") (pin "2") (pinfunction "D2_2") (pintype "passive"))
      (node (ref "T25") (pin "4") (pinfunction "D3_4") (pintype "passive"))
    )
    (net (code "154") (name "VPP") (class "Default")
      (node (ref "C13") (pin "2") (pinfunction "C2_2") (pintype "passive"))
      (node (ref "L11") (pin "2") (pinfunction "2_2") (pintype "bidirectional"))
      (node (ref "L21") (pin "2") (pinfunction "2_2") (pintype "bidirectional"))
      (node (ref "R23") (pin "2") (pinfunction "2_2") (pintype "passive"))
      (node (ref "X9") (pin "9") (pinfunction "S_9") (pintype "passive"))
    )
    (net (code "155") (name "VPPCHG") (class "Default")
      (node (ref "C69") (pin "2") (pinfunction "C2_2") (pintype "passive"))
      (node (ref "C70") (pin "2") (pinfunction "C2_2") (pintype "passive"))
      (node (ref "RL7") (pin "3") (pinfunction "DS2_3") (pintype "passive"))
      (node (ref "T4") (pin "2") (pinfunction "D1_2") (pintype "passive"))
      (node (ref "T4") (pin "4") (pinfunction "D2_4") (pintype "passive"))
    )
    (net (code "156") (name "VPP_CHARGE") (class "Default")
      (node (ref "L3") (pin "2") (pinfunction "2_2") (pintype "bidirectional"))
      (node (ref "U5") (pin "32") (pinfunction "P0.3/IRQ0/SS1_32") (pintype "bidirectional"))
    )
    (net (code "157") (name "unconnected-(D1-Pad3)") (class "Default")
      (node (ref "D1") (pin "3") (pinfunction "3_3") (pintype "bidirectional"))
    )
    (net (code "158") (name "unconnected-(D8-C2-Pad2)") (class "Default")
      (node (ref "D8") (pin "2") (pinfunction "C2_2") (pintype "passive"))
    )
    (net (code "159") (name "unconnected-(D22-C2-Pad2)") (class "Default")
      (node (ref "D22") (pin "2") (pinfunction "C2_2") (pintype "passive"))
    )
    (net (code "160") (name "unconnected-(U1-NC-Pad4)") (class "Default")
      (node (ref "U1") (pin "4") (pinfunction "NC_4") (pintype "no_connect"))
    )
    (net (code "161") (name "unconnected-(U2-NC-Pad4)") (class "Default")
      (node (ref "U2") (pin "4") (pinfunction "NC_4") (pintype "no_connect"))
    )
    (net (code "162") (name "unconnected-(U3-LBO-Pad4)") (class "Default")
      (node (ref "U3") (pin "4") (pinfunction "LBO_4") (pintype "output"))
    )
    (net (code "163") (name "unconnected-(U5-AIN1{slash}VBIASO-Pad9)") (class "Default")
      (node (ref "U5") (pin "9") (pinfunction "AIN1/VBIASO_9") (pintype "bidirectional"))
    )
    (net (code "164") (name "unconnected-(U5-P0.7{slash}POR{slash}SOUT-Pad36)") (class "Default")
      (node (ref "U5") (pin "36") (pinfunction "P0.7/POR/SOUT_36") (pintype "bidirectional"))
    )
    (net (code "165") (name "unconnected-(U5-VREF_IN--Pad15)") (class "Default")
      (node (ref "U5") (pin "15") (pinfunction "VREF_IN-_15") (pintype "bidirectional"))
    )
    (net (code "166") (name "unconnected-(U5-VRESF_IN+-Pad14)") (class "Default")
      (node (ref "U5") (pin "14") (pinfunction "VRESF_IN+_14") (pintype "bidirectional"))
    )
    (net (code "167") (name "unconnected-(U13-~{DONE}-Pad1)") (class "Default")
      (node (ref "U13") (pin "1") (pinfunction "~{DONE}_1") (pintype "bidirectional"))
    )
    (net (code "168") (name "unconnected-(U18-LO--Pad11)") (class "Default")
      (node (ref "U18") (pin "11") (pinfunction "LO-_11") (pintype "bidirectional"))
    )
    (net (code "169") (name "unconnected-(X6I-S-Pad17)") (class "Default")
      (node (ref "X6") (pin "17") (pinfunction "S_17") (pintype "passive"))
    )
    (net (code "170") (name "unconnected-(X6J-S-Pad18)") (class "Default")
      (node (ref "X6") (pin "18") (pinfunction "S_18") (pintype "passive"))
    )
    (net (code "171") (name "unconnected-(X6K-S-Pad19)") (class "Default")
      (node (ref "X6") (pin "19") (pinfunction "S_19") (pintype "passive"))
    )
    (net (code "172") (name "unconnected-(X6M-S-Pad20)") (class "Default")
      (node (ref "X6") (pin "20") (pinfunction "S_20") (pintype "passive"))
    )
    (net (code "173") (name "unconnected-(X7A-S-Pad1)") (class "Default")
      (node (ref "X7") (pin "1") (pinfunction "S_1") (pintype "passive"))
    )
    (net (code "174") (name "unconnected-(X7B-S-Pad10)") (class "Default")
      (node (ref "X7") (pin "10") (pinfunction "S_10") (pintype "passive"))
    )
    (net (code "175") (name "unconnected-(X7C-S-Pad11)") (class "Default")
      (node (ref "X7") (pin "11") (pinfunction "S_11") (pintype "passive"))
    )
    (net (code "176") (name "unconnected-(X7F-S-Pad14)") (class "Default")
      (node (ref "X7") (pin "14") (pinfunction "S_14") (pintype "passive"))
    )
    (net (code "177") (name "unconnected-(X7G-S-Pad15)") (class "Default")
      (node (ref "X7") (pin "15") (pinfunction "S_15") (pintype "passive"))
    )
    (net (code "178") (name "unconnected-(X7L-S-Pad2)") (class "Default")
      (node (ref "X7") (pin "2") (pinfunction "S_2") (pintype "passive"))
    )
    (net (code "179") (name "unconnected-(X7N-S-Pad3)") (class "Default")
      (node (ref "X7") (pin "3") (pinfunction "S_3") (pintype "passive"))
    )
    (net (code "180") (name "unconnected-(X7O-S-Pad4)") (class "Default")
      (node (ref "X7") (pin "4") (pinfunction "S_4") (pintype "passive"))
    )
    (net (code "181") (name "unconnected-(X7P-S-Pad5)") (class "Default")
      (node (ref "X7") (pin "5") (pinfunction "S_5") (pintype "passive"))
    )
  )
)
